# ACB-Light-R1_0-J01.net
KiCad netlist of a schematic drawn in EAGLE
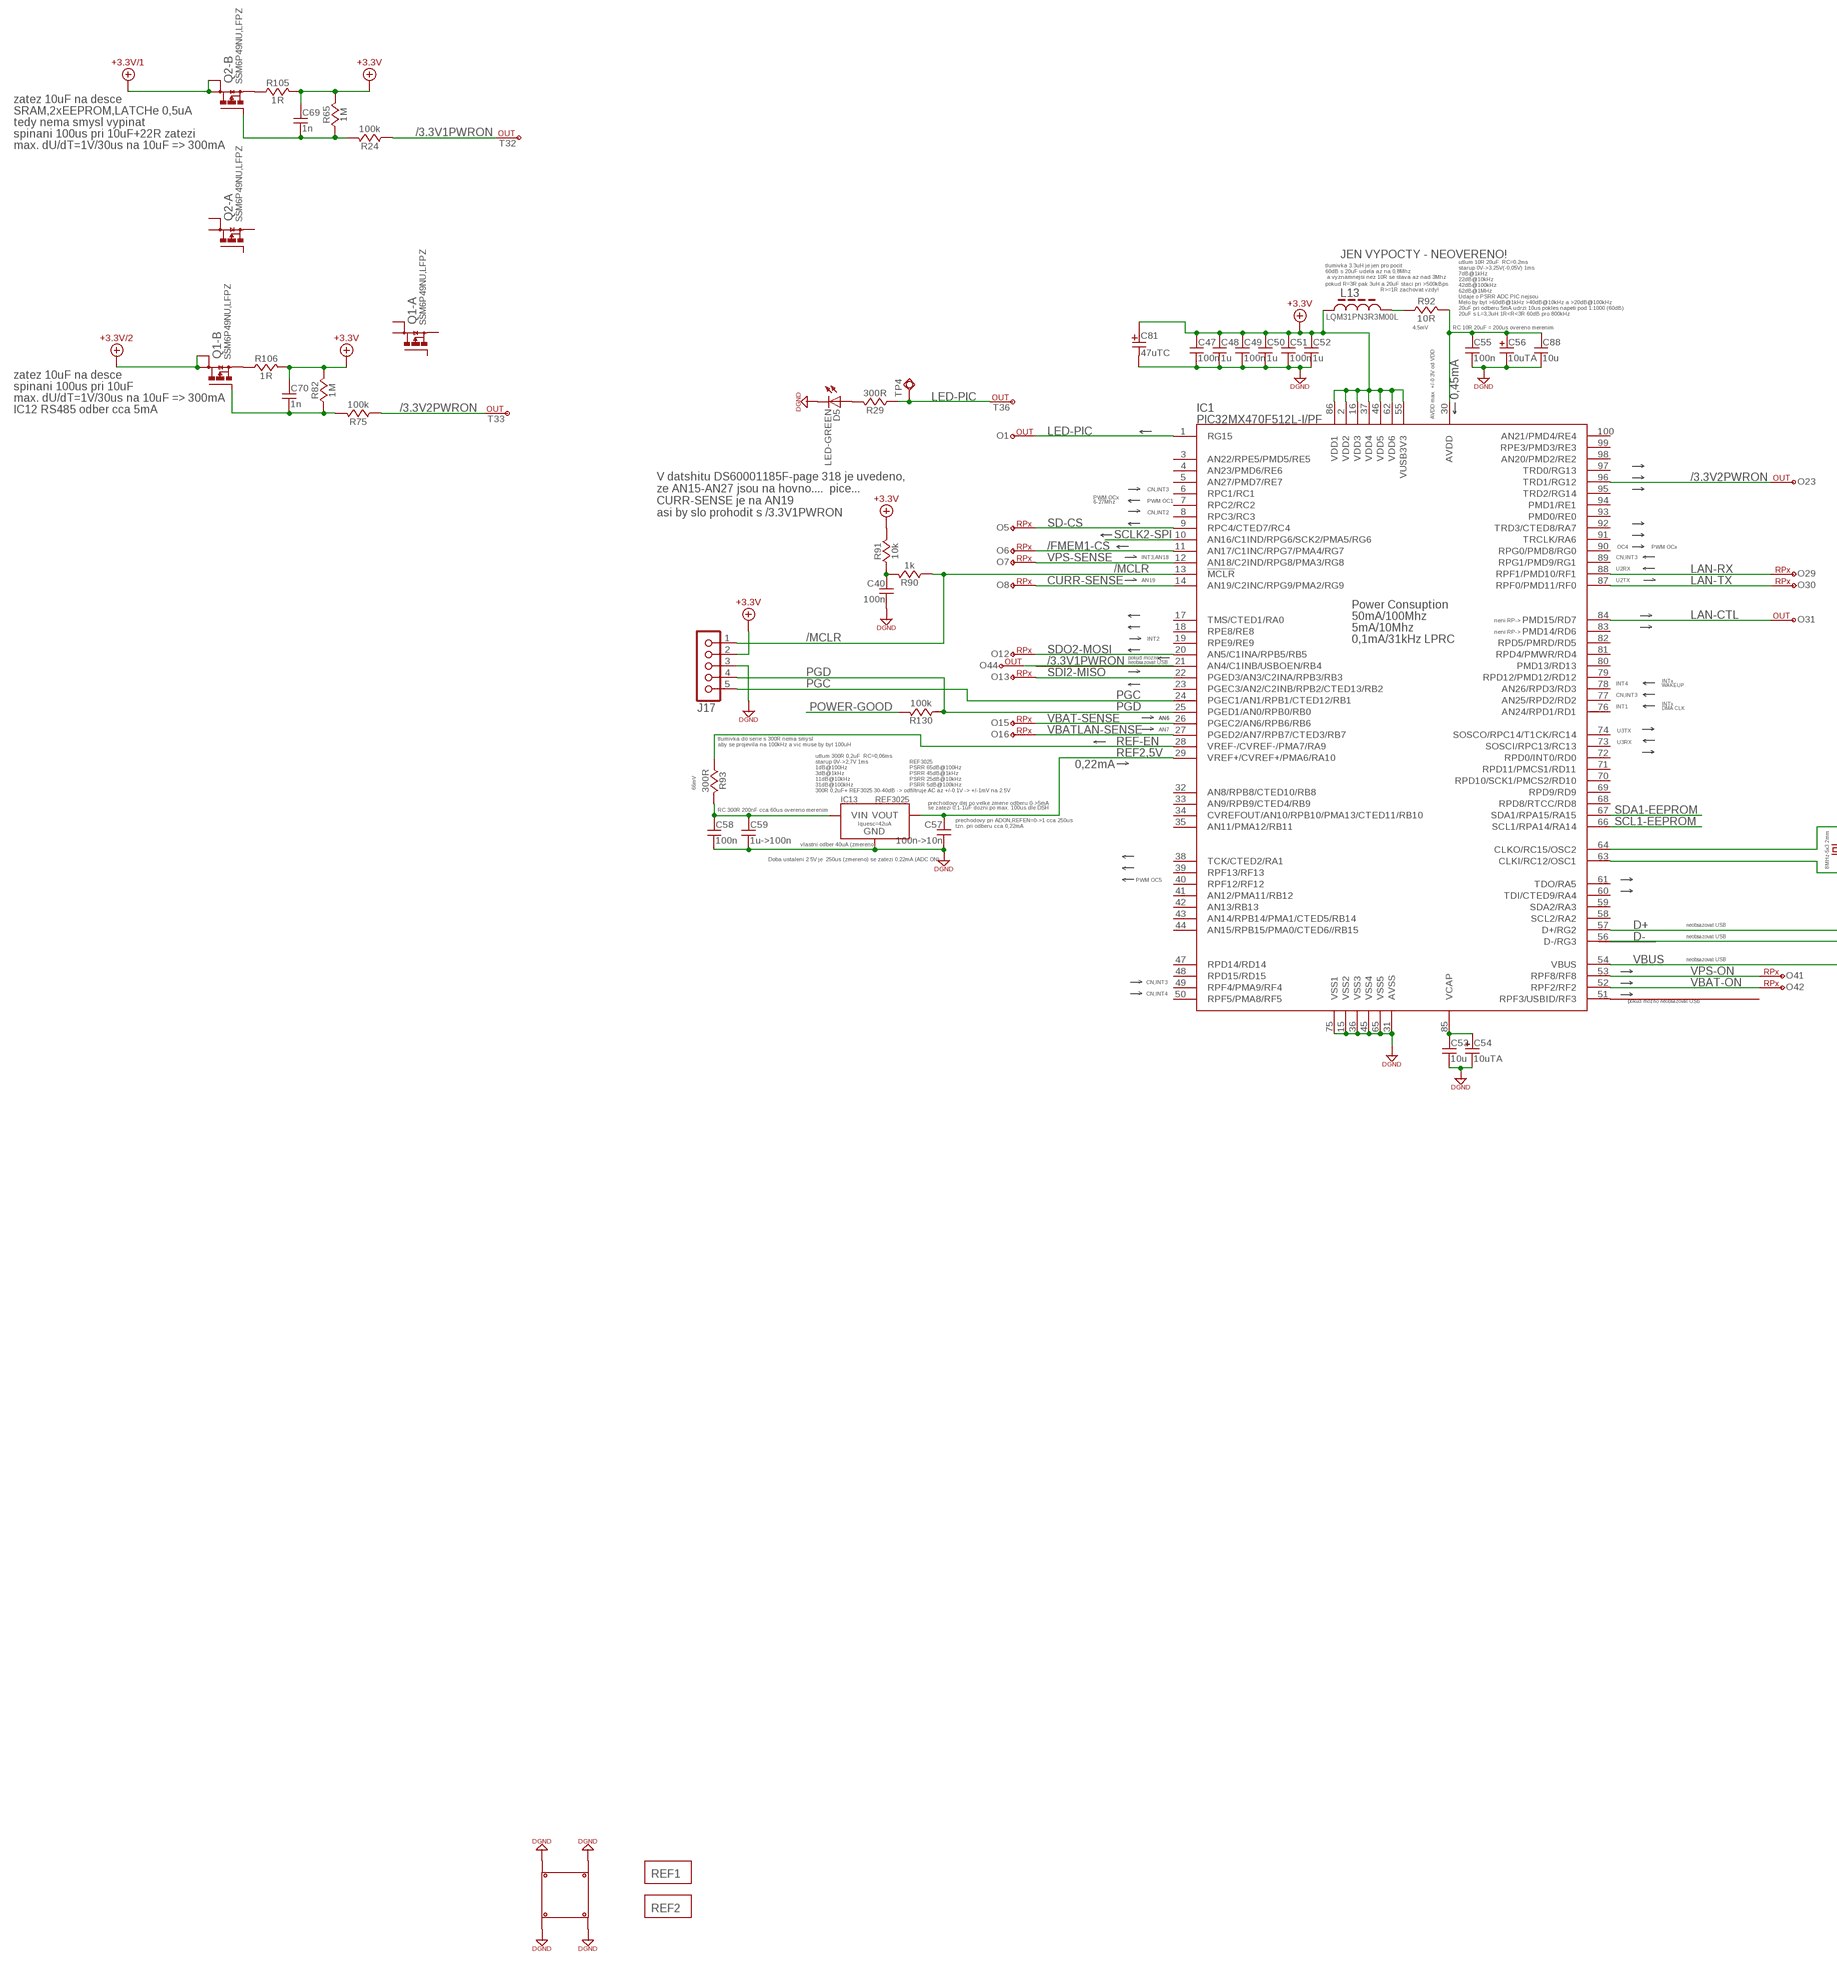
[diagram p0: schematic, sheet 1, part 1 of 3]
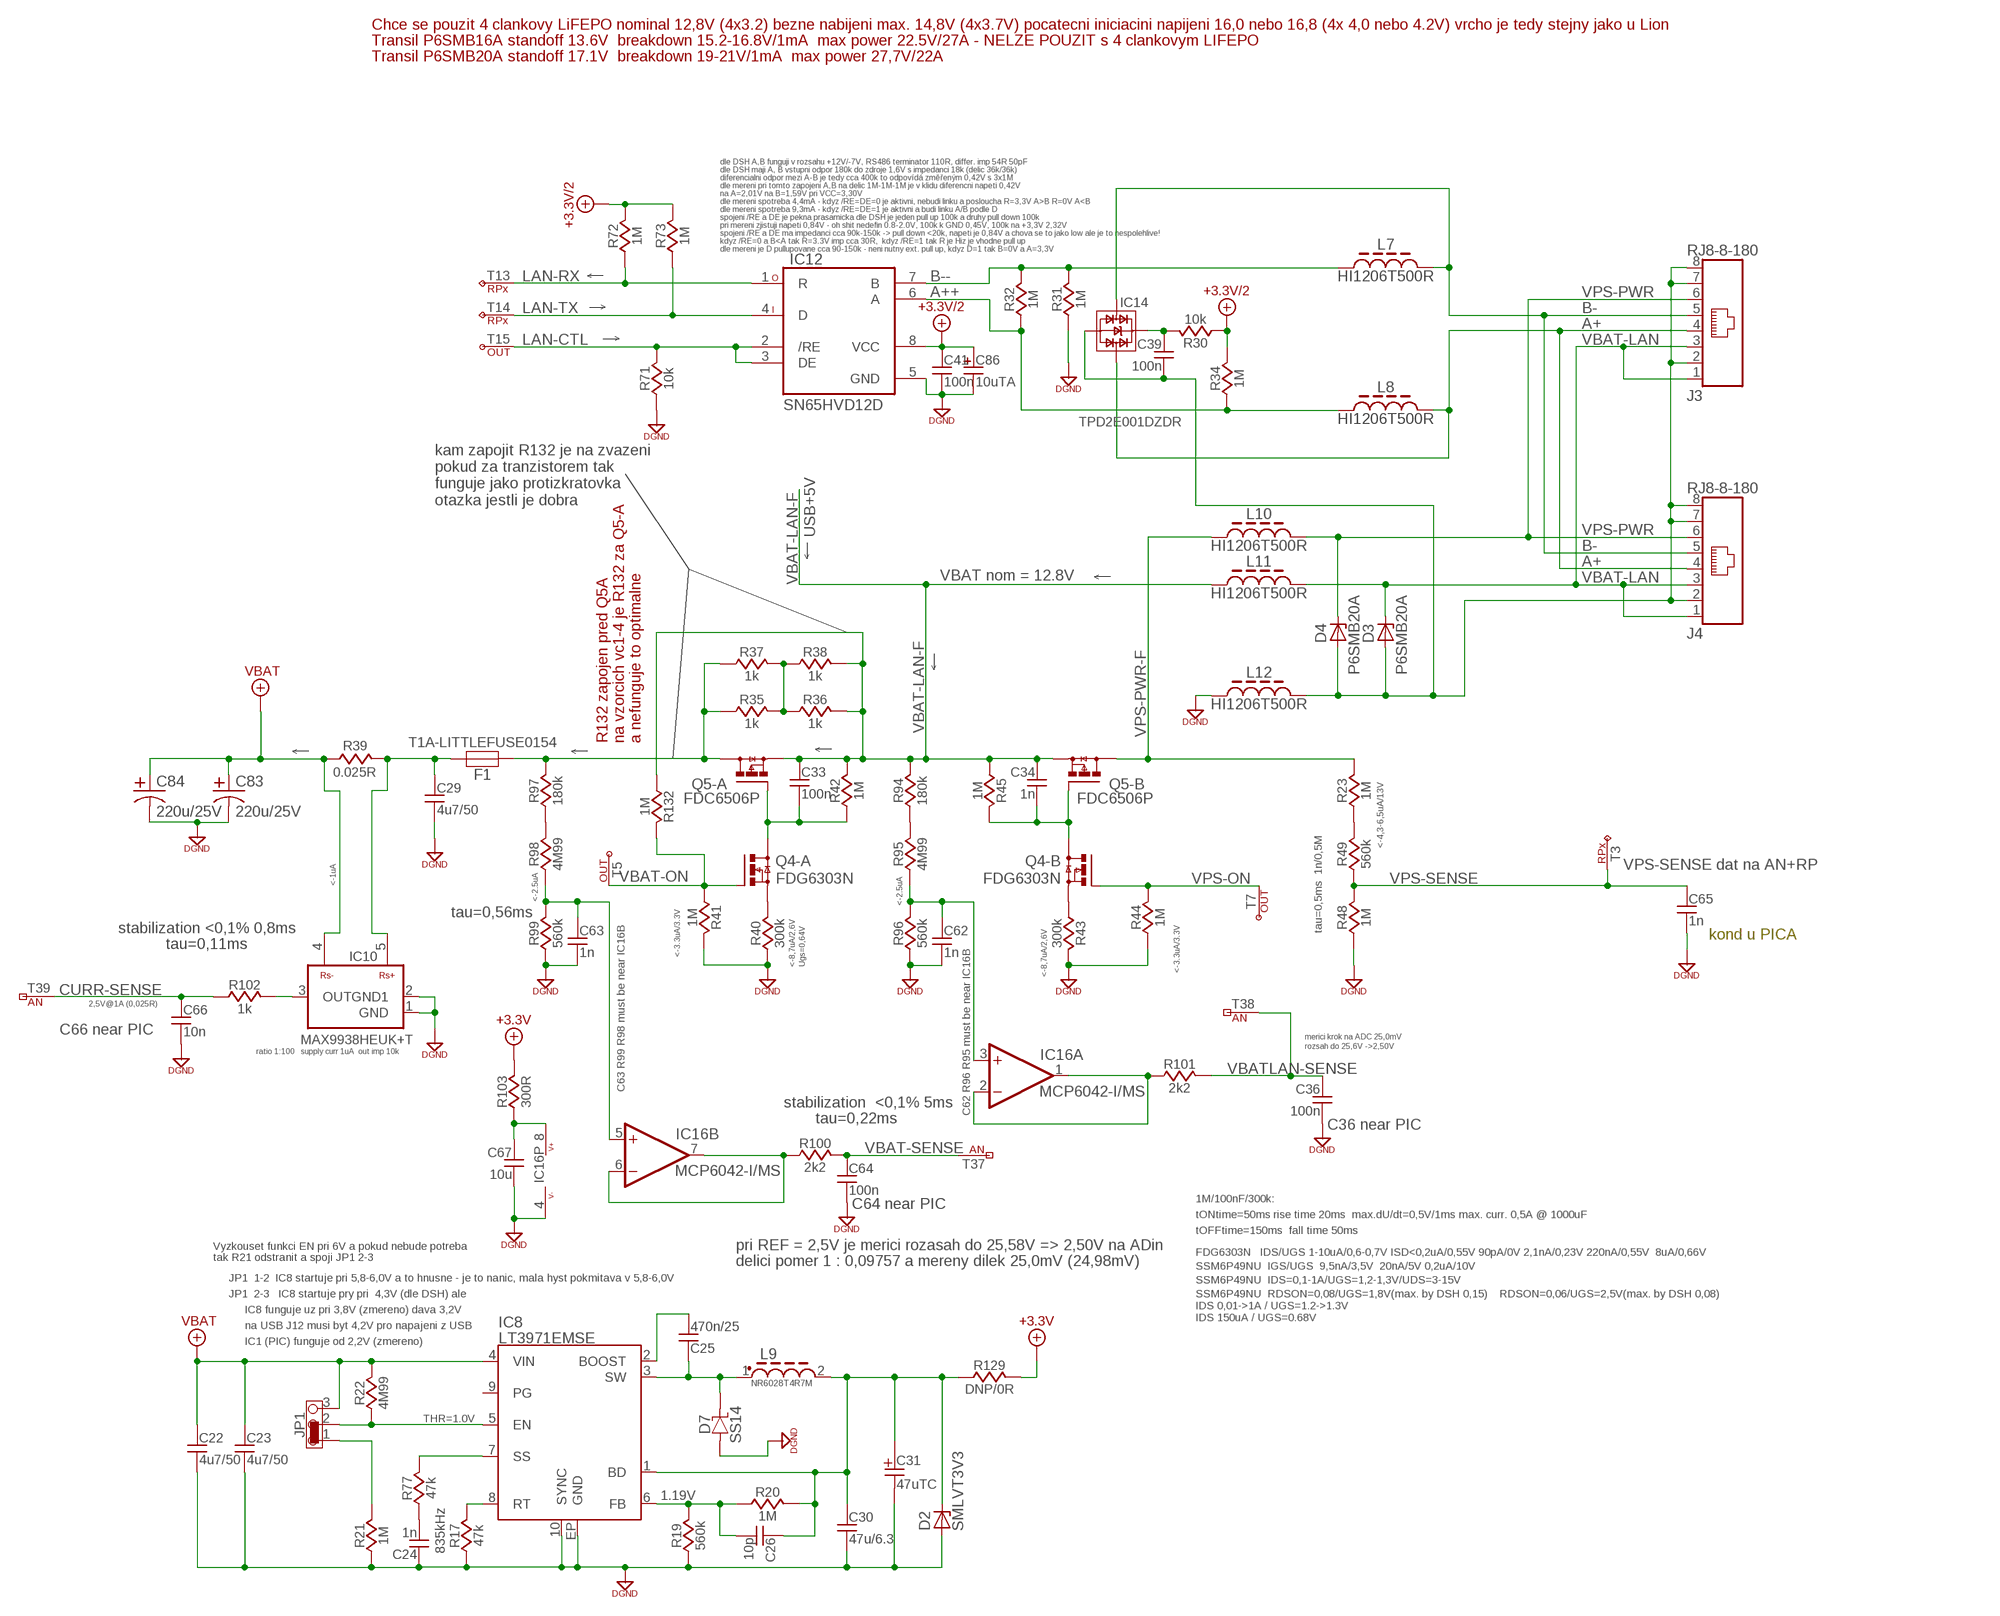
[diagram p1: schematic, sheet 1, part 2 of 3]
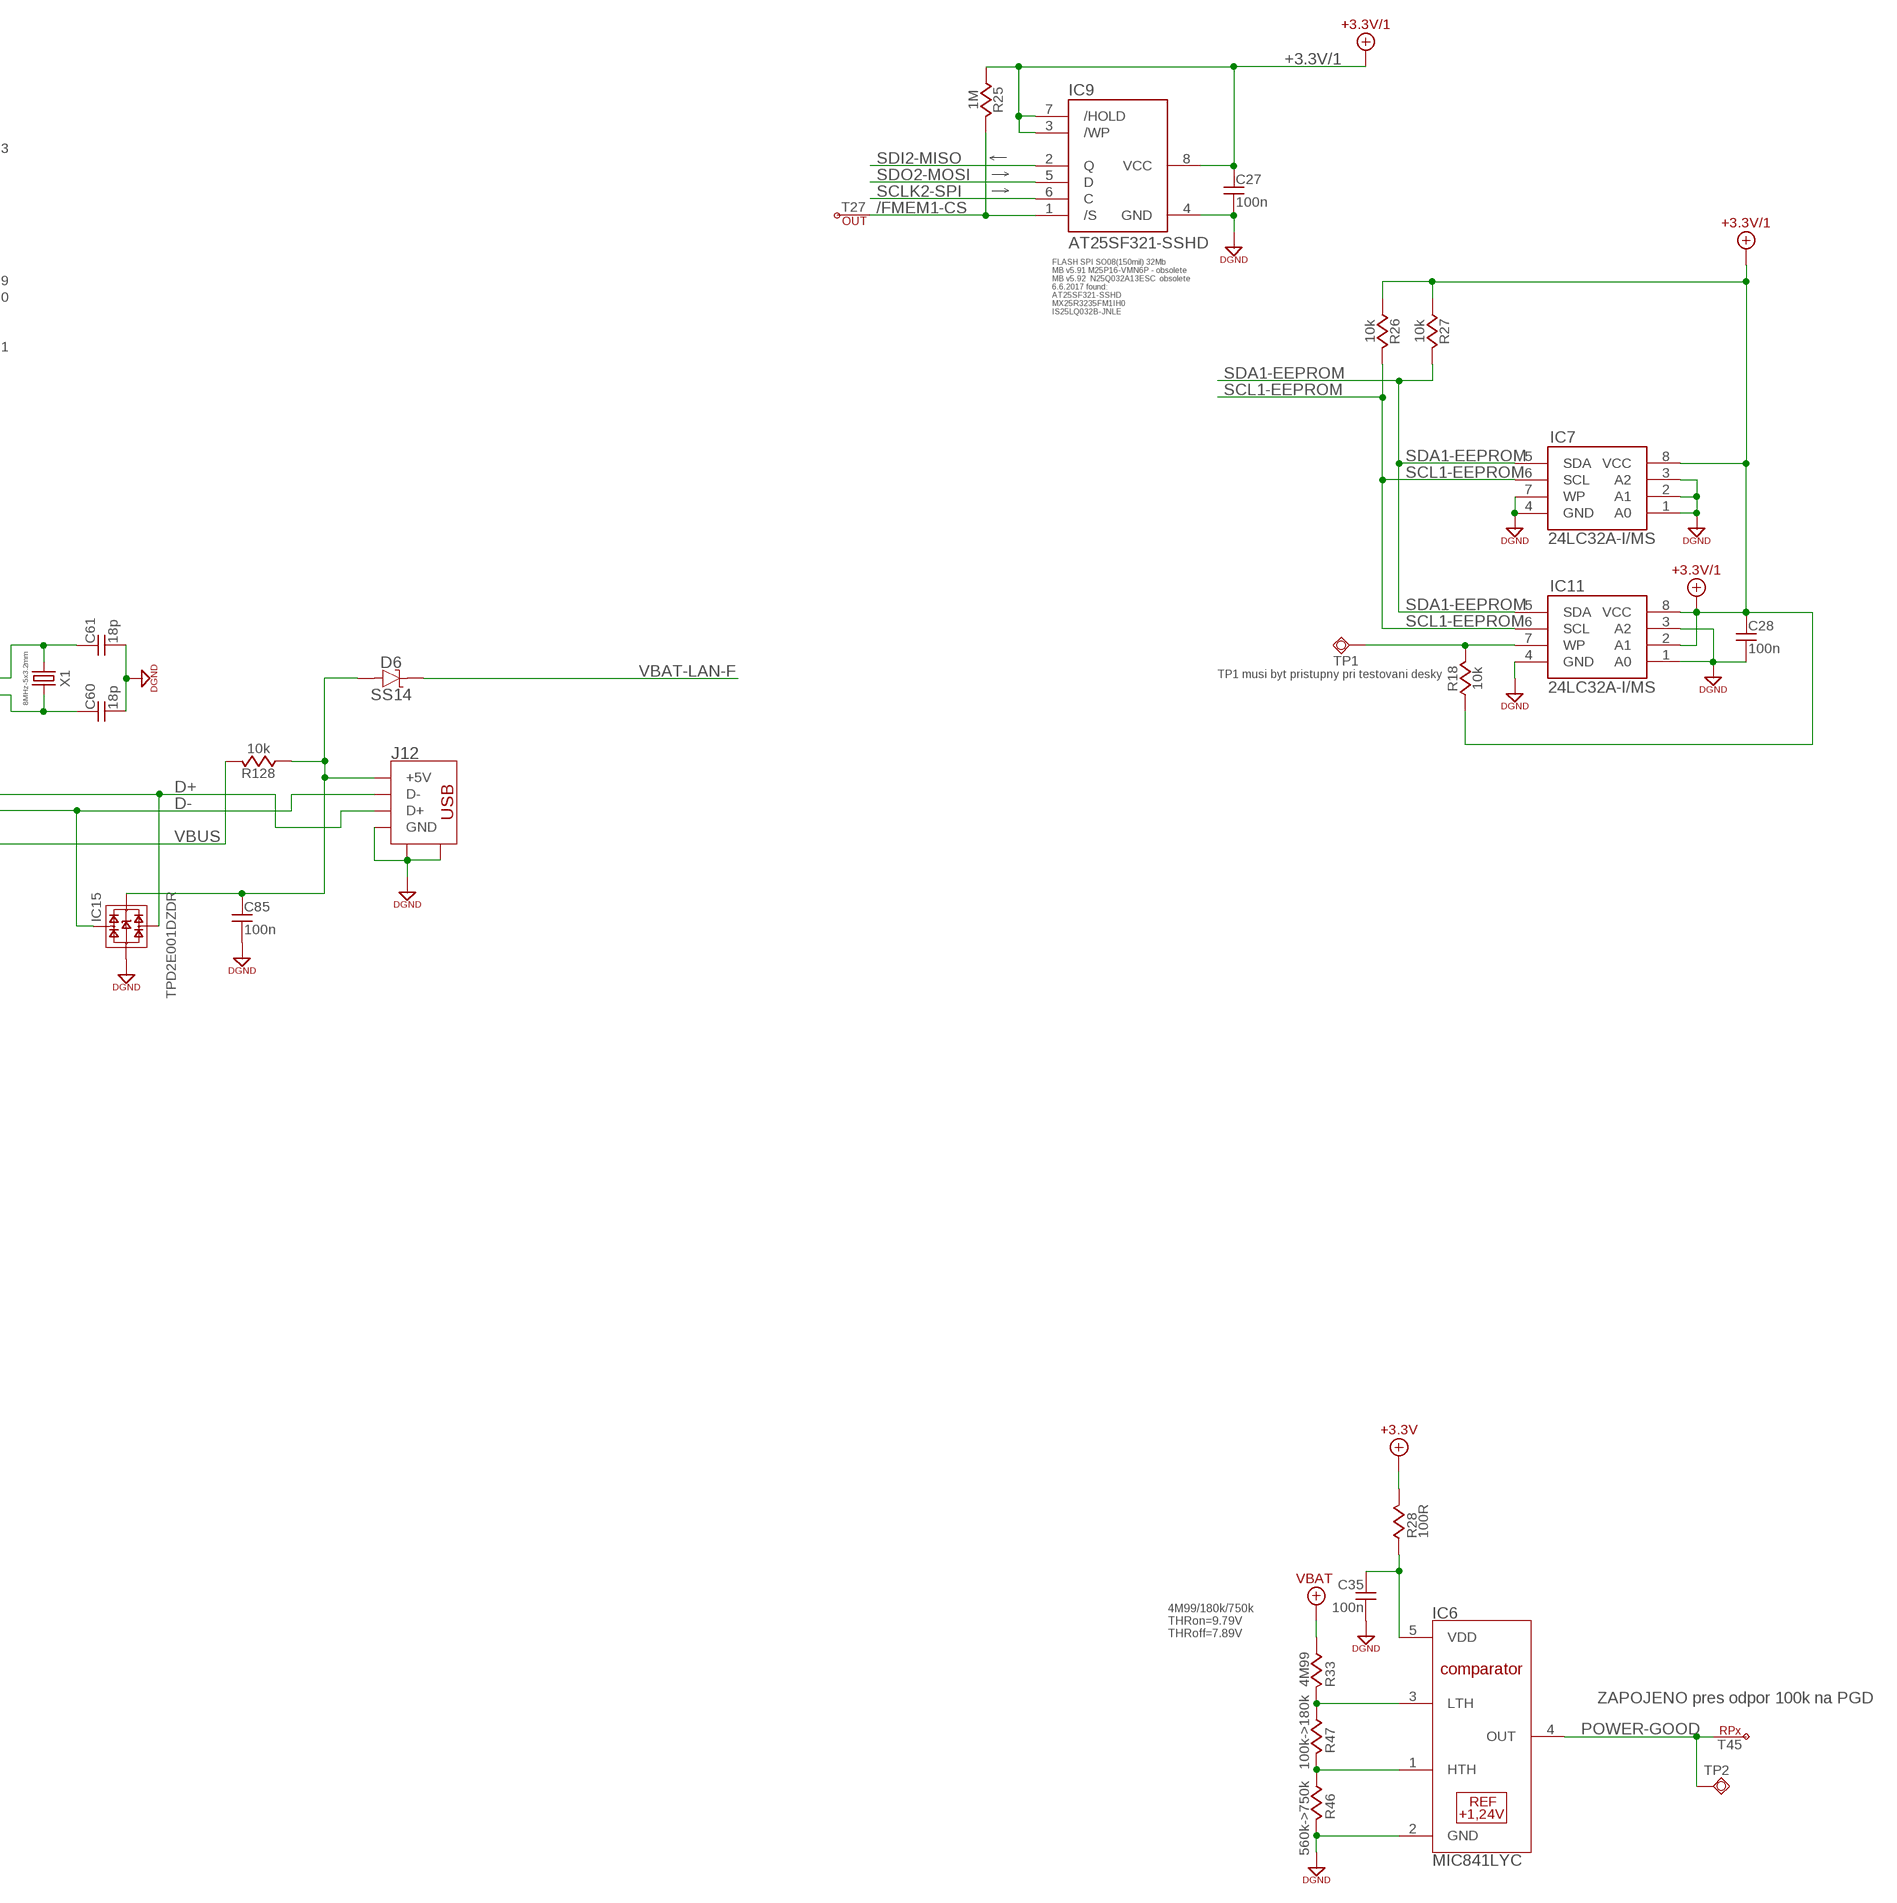
[diagram p2: schematic, sheet 1, part 3 of 3]

(export (version "E")
  (design (tool "Eeschema 10.0.6"))
  (components
    (comp (ref "C22")
      (value "4u7/50")
      (footprint "eagle-import:1206")
      (libsource (lib "eagle-import") (part "C-1206"))
    )
    (comp (ref "C23")
      (value "4u7/50")
      (footprint "eagle-import:1206")
      (libsource (lib "eagle-import") (part "C-1206"))
    )
    (comp (ref "C24")
      (value "1n")
      (footprint "eagle-import:0603")
      (libsource (lib "eagle-import") (part "C-0603"))
    )
    (comp (ref "C25")
      (value "470n/25")
      (footprint "eagle-import:0603")
      (libsource (lib "eagle-import") (part "C-0603"))
    )
    (comp (ref "C26")
      (value "10p")
      (footprint "eagle-import:0603")
      (libsource (lib "eagle-import") (part "C-0603"))
    )
    (comp (ref "C27")
      (value "100n")
      (footprint "eagle-import:0603")
      (libsource (lib "eagle-import") (part "C-0603"))
    )
    (comp (ref "C28")
      (value "100n")
      (footprint "eagle-import:0603")
      (libsource (lib "eagle-import") (part "C-0603"))
    )
    (comp (ref "C29")
      (value "4u7/50")
      (footprint "eagle-import:1206")
      (libsource (lib "eagle-import") (part "C-1206"))
    )
    (comp (ref "C30")
      (value "47u/6.3")
      (footprint "eagle-import:1206")
      (libsource (lib "eagle-import") (part "C-1206"))
    )
    (comp (ref "C31")
      (value "47uTC")
      (footprint "eagle-import:CT-C")
      (libsource (lib "eagle-import") (part "CT-C"))
    )
    (comp (ref "C33")
      (value "100n")
      (footprint "eagle-import:0603")
      (libsource (lib "eagle-import") (part "C-0603"))
    )
    (comp (ref "C34")
      (value "1n")
      (footprint "eagle-import:0603")
      (libsource (lib "eagle-import") (part "C-0603"))
    )
    (comp (ref "C35")
      (value "100n")
      (footprint "eagle-import:0603")
      (libsource (lib "eagle-import") (part "C-0603"))
    )
    (comp (ref "C36")
      (value "100n")
      (footprint "eagle-import:0603")
      (libsource (lib "eagle-import") (part "C-0603"))
    )
    (comp (ref "C39")
      (value "100n")
      (footprint "eagle-import:0603")
      (libsource (lib "eagle-import") (part "C-0603"))
    )
    (comp (ref "C40")
      (value "100n")
      (footprint "eagle-import:0603")
      (libsource (lib "eagle-import") (part "C-0603"))
    )
    (comp (ref "C41")
      (value "100n")
      (footprint "eagle-import:0603")
      (libsource (lib "eagle-import") (part "C-0603"))
    )
    (comp (ref "C47")
      (value "100n")
      (footprint "eagle-import:0603")
      (libsource (lib "eagle-import") (part "C-0603"))
    )
    (comp (ref "C48")
      (value "1u")
      (footprint "eagle-import:0603")
      (libsource (lib "eagle-import") (part "C-0603"))
    )
    (comp (ref "C49")
      (value "100n")
      (footprint "eagle-import:0603")
      (libsource (lib "eagle-import") (part "C-0603"))
    )
    (comp (ref "C50")
      (value "1u")
      (footprint "eagle-import:0603")
      (libsource (lib "eagle-import") (part "C-0603"))
    )
    (comp (ref "C51")
      (value "100n")
      (footprint "eagle-import:0603")
      (libsource (lib "eagle-import") (part "C-0603"))
    )
    (comp (ref "C52")
      (value "1u")
      (footprint "eagle-import:0603")
      (libsource (lib "eagle-import") (part "C-0603"))
    )
    (comp (ref "C53")
      (value "10u")
      (footprint "eagle-import:0603")
      (libsource (lib "eagle-import") (part "C-0603"))
    )
    (comp (ref "C54")
      (value "10uTA")
      (footprint "eagle-import:1206-POL-C")
      (libsource (lib "eagle-import") (part "CT-1206"))
    )
    (comp (ref "C55")
      (value "100n")
      (footprint "eagle-import:0603")
      (libsource (lib "eagle-import") (part "C-0603"))
    )
    (comp (ref "C56")
      (value "10uTA")
      (footprint "eagle-import:1206-POL-C")
      (libsource (lib "eagle-import") (part "CT-1206"))
    )
    (comp (ref "C57")
      (value "100n->10n")
      (footprint "eagle-import:0603")
      (libsource (lib "eagle-import") (part "C-0603"))
    )
    (comp (ref "C58")
      (value "100n")
      (footprint "eagle-import:0603")
      (libsource (lib "eagle-import") (part "C-0603"))
    )
    (comp (ref "C59")
      (value "1u->100n")
      (footprint "eagle-import:0603")
      (libsource (lib "eagle-import") (part "C-0603"))
    )
    (comp (ref "C60")
      (value "18p")
      (footprint "eagle-import:0603")
      (libsource (lib "eagle-import") (part "C-0603"))
    )
    (comp (ref "C61")
      (value "18p")
      (footprint "eagle-import:0603")
      (libsource (lib "eagle-import") (part "C-0603"))
    )
    (comp (ref "C62")
      (value "1n")
      (footprint "eagle-import:0603")
      (libsource (lib "eagle-import") (part "C-0603"))
    )
    (comp (ref "C63")
      (value "1n")
      (footprint "eagle-import:0603")
      (libsource (lib "eagle-import") (part "C-0603"))
    )
    (comp (ref "C64")
      (value "100n")
      (footprint "eagle-import:0603")
      (libsource (lib "eagle-import") (part "C-0603"))
    )
    (comp (ref "C65")
      (value "1n")
      (footprint "eagle-import:0603")
      (libsource (lib "eagle-import") (part "C-0603"))
    )
    (comp (ref "C66")
      (value "10n")
      (footprint "eagle-import:0603")
      (libsource (lib "eagle-import") (part "C-0603"))
    )
    (comp (ref "C67")
      (value "10u")
      (footprint "eagle-import:0603")
      (libsource (lib "eagle-import") (part "C-0603"))
    )
    (comp (ref "C69")
      (value "1n")
      (footprint "eagle-import:0603")
      (libsource (lib "eagle-import") (part "C-0603"))
    )
    (comp (ref "C70")
      (value "1n")
      (footprint "eagle-import:0603")
      (libsource (lib "eagle-import") (part "C-0603"))
    )
    (comp (ref "C81")
      (value "47uTC")
      (footprint "eagle-import:CT-C")
      (libsource (lib "eagle-import") (part "CT-C"))
    )
    (comp (ref "C83")
      (value "220u/25V")
      (footprint "eagle-import:CAP_8MM_DIA_SMT")
      (libsource (lib "eagle-import") (part "CAP-ELEC-SMD-8MM"))
    )
    (comp (ref "C84")
      (value "220u/25V")
      (footprint "eagle-import:CAP_8MM_DIA_SMT")
      (libsource (lib "eagle-import") (part "CAP-ELEC-SMD-8MM"))
    )
    (comp (ref "C85")
      (value "100n")
      (footprint "eagle-import:0603")
      (libsource (lib "eagle-import") (part "C-0603"))
    )
    (comp (ref "C86")
      (value "10uTA")
      (footprint "eagle-import:1206-POL-C")
      (libsource (lib "eagle-import") (part "CT-1206"))
    )
    (comp (ref "C88")
      (value "10u")
      (footprint "eagle-import:0603")
      (libsource (lib "eagle-import") (part "C-0603"))
    )
    (comp (ref "D2")
      (value "SMLVT3V3")
      (footprint "eagle-import:SMA")
      (libsource (lib "eagle-import") (part "SMLVT3V3"))
    )
    (comp (ref "D3")
      (value "P6SMB20A")
      (footprint "eagle-import:SMB")
      (libsource (lib "eagle-import") (part "P6SMB"))
    )
    (comp (ref "D4")
      (value "P6SMB20A")
      (footprint "eagle-import:SMB")
      (libsource (lib "eagle-import") (part "P6SMB"))
    )
    (comp (ref "D5")
      (value "LED-GREEN")
      (footprint "eagle-import:0805-POL-D")
      (libsource (lib "eagle-import") (part "LED-0805"))
    )
    (comp (ref "D6")
      (value "SS14")
      (footprint "eagle-import:SMA")
      (libsource (lib "eagle-import") (part "DS-SMA"))
    )
    (comp (ref "D7")
      (value "SS14")
      (footprint "eagle-import:SMA")
      (libsource (lib "eagle-import") (part "DS-SMA"))
    )
    (comp (ref "F1")
      (value "T1A-LITTLEFUSE0154")
      (footprint "eagle-import:LITTLEFUSE0154")
      (libsource (lib "eagle-import") (part "POJISTKA-LITTLEFUSE0154"))
    )
    (comp (ref "IC1")
      (value "PIC32MX470F512L-I/PF")
      (footprint "eagle-import:TQFP100_14X14_0,5MM")
      (libsource (lib "eagle-import") (part "PIC32MX470F512L-I/PF"))
    )
    (comp (ref "IC6")
      (value "MIC841LYC")
      (footprint "eagle-import:SC-70-5")
      (libsource (lib "eagle-import") (part "MIC841LYC"))
    )
    (comp (ref "IC7")
      (value "24LC32A-I/MS")
      (footprint "eagle-import:MSOP-08")
      (libsource (lib "eagle-import") (part "24-I/MS"))
    )
    (comp (ref "IC8")
      (value "LT3971EMSE")
      (footprint "eagle-import:MSOP10EXP")
      (libsource (lib "eagle-import") (part "LT3971EMSE"))
    )
    (comp (ref "IC9")
      (value "AT25SF321-SSHD")
      (footprint "eagle-import:SO-08")
      (libsource (lib "eagle-import") (part "M25P16-VMN6P"))
    )
    (comp (ref "IC10")
      (value "MAX9938HEUK+T")
      (footprint "eagle-import:SOT23-5")
      (libsource (lib "eagle-import") (part "TSM9938HEUK+T"))
    )
    (comp (ref "IC11")
      (value "24LC32A-I/MS")
      (footprint "eagle-import:MSOP-08")
      (libsource (lib "eagle-import") (part "24-I/MS"))
    )
    (comp (ref "IC12")
      (value "SN65HVD12D")
      (footprint "eagle-import:SO08")
      (libsource (lib "eagle-import") (part "SN65HVD3082ED"))
    )
    (comp (ref "IC13")
      (value "REF3025")
      (footprint "eagle-import:SOT23")
      (libsource (lib "eagle-import") (part "REF3025"))
    )
    (comp (ref "IC14")
      (value "TPD2E001DZDR")
      (footprint "eagle-import:SOT-143")
      (libsource (lib "eagle-import") (part "SR05.TCT"))
    )
    (comp (ref "IC15")
      (value "TPD2E001DZDR")
      (footprint "eagle-import:SOT-143")
      (libsource (lib "eagle-import") (part "SR05.TCT"))
    )
    (comp (ref "IC16")
      (value "MCP6042-I/MS")
      (footprint "eagle-import:MSOP-08")
      (libsource (lib "eagle-import") (part "MCP6042-I/MS"))
    )
    (comp (ref "J3")
      (value "RJ8-8-180")
      (footprint "eagle-import:RJ8-8-180")
      (libsource (lib "eagle-import") (part "RJ8-8-180"))
    )
    (comp (ref "J4")
      (value "RJ8-8-180")
      (footprint "eagle-import:RJ8-8-180")
      (libsource (lib "eagle-import") (part "RJ8-8-180"))
    )
    (comp (ref "J12")
      (value "USB_A_180")
      (footprint "eagle-import:USB_B_180")
      (libsource (lib "eagle-import") (part "USB_B_180"))
    )
    (comp (ref "J17")
      (value "DNP-open-hole")
      (footprint "eagle-import:MA05-1")
      (libsource (lib "eagle-import") (part "MA05-1"))
    )
    (comp (ref "JP1")
      (value "JP3CLOSE12")
      (footprint "eagle-import:JP3CLOSE12")
      (libsource (lib "eagle-import") (part "JP3CLOSE12"))
    )
    (comp (ref "L7")
      (value "HI1206T500R")
      (footprint "eagle-import:1206")
      (libsource (lib "eagle-import") (part "L-1206"))
    )
    (comp (ref "L8")
      (value "HI1206T500R")
      (footprint "eagle-import:1206")
      (libsource (lib "eagle-import") (part "L-1206"))
    )
    (comp (ref "L9")
      (value "NR6028T4R7M")
      (footprint "eagle-import:NR6028")
      (libsource (lib "eagle-import") (part "NR6028"))
    )
    (comp (ref "L10")
      (value "HI1206T500R")
      (footprint "eagle-import:1206")
      (libsource (lib "eagle-import") (part "L-1206"))
    )
    (comp (ref "L11")
      (value "HI1206T500R")
      (footprint "eagle-import:1206")
      (libsource (lib "eagle-import") (part "L-1206"))
    )
    (comp (ref "L12")
      (value "HI1206T500R")
      (footprint "eagle-import:1206")
      (libsource (lib "eagle-import") (part "L-1206"))
    )
    (comp (ref "L13")
      (value "LQM31PN3R3M00L")
      (footprint "eagle-import:1206")
      (libsource (lib "eagle-import") (part "L-1206"))
    )
    (comp (ref "O1")
      (value "PIC-OUT")
      (footprint "eagle-import:TEMP-PAD")
      (libsource (lib "eagle-import") (part "PIC-OUT"))
    )
    (comp (ref "O5")
      (value "PIC-RPX")
      (footprint "eagle-import:TEMP-PAD")
      (libsource (lib "eagle-import") (part "PIC-RPX"))
    )
    (comp (ref "O6")
      (value "PIC-RPX")
      (footprint "eagle-import:TEMP-PAD")
      (libsource (lib "eagle-import") (part "PIC-RPX"))
    )
    (comp (ref "O7")
      (value "PIC-RPX")
      (footprint "eagle-import:TEMP-PAD")
      (libsource (lib "eagle-import") (part "PIC-RPX"))
    )
    (comp (ref "O8")
      (value "PIC-RPX")
      (footprint "eagle-import:TEMP-PAD")
      (libsource (lib "eagle-import") (part "PIC-RPX"))
    )
    (comp (ref "O12")
      (value "PIC-RPX")
      (footprint "eagle-import:TEMP-PAD")
      (libsource (lib "eagle-import") (part "PIC-RPX"))
    )
    (comp (ref "O13")
      (value "PIC-RPX")
      (footprint "eagle-import:TEMP-PAD")
      (libsource (lib "eagle-import") (part "PIC-RPX"))
    )
    (comp (ref "O15")
      (value "PIC-RPX")
      (footprint "eagle-import:TEMP-PAD")
      (libsource (lib "eagle-import") (part "PIC-RPX"))
    )
    (comp (ref "O16")
      (value "PIC-RPX")
      (footprint "eagle-import:TEMP-PAD")
      (libsource (lib "eagle-import") (part "PIC-RPX"))
    )
    (comp (ref "O23")
      (value "PIC-OUT")
      (footprint "eagle-import:TEMP-PAD")
      (libsource (lib "eagle-import") (part "PIC-OUT"))
    )
    (comp (ref "O29")
      (value "PIC-RPX")
      (footprint "eagle-import:TEMP-PAD")
      (libsource (lib "eagle-import") (part "PIC-RPX"))
    )
    (comp (ref "O30")
      (value "PIC-RPX")
      (footprint "eagle-import:TEMP-PAD")
      (libsource (lib "eagle-import") (part "PIC-RPX"))
    )
    (comp (ref "O31")
      (value "PIC-OUT")
      (footprint "eagle-import:TEMP-PAD")
      (libsource (lib "eagle-import") (part "PIC-OUT"))
    )
    (comp (ref "O41")
      (value "PIC-RPX")
      (footprint "eagle-import:TEMP-PAD")
      (libsource (lib "eagle-import") (part "PIC-RPX"))
    )
    (comp (ref "O42")
      (value "PIC-RPX")
      (footprint "eagle-import:TEMP-PAD")
      (libsource (lib "eagle-import") (part "PIC-RPX"))
    )
    (comp (ref "O44")
      (value "PIC-OUT")
      (footprint "eagle-import:TEMP-PAD")
      (libsource (lib "eagle-import") (part "PIC-OUT"))
    )
    (comp (ref "PCB1")
      (value "PCB-ACB")
      (footprint "eagle-import:PCB-ACB")
      (libsource (lib "eagle-import") (part "PCB-ACB-1"))
    )
    (comp (ref "Q1")
      (value "SSM6P49NU,LFPZ")
      (footprint "eagle-import:MICRO_FET")
      (libsource (lib "eagle-import") (part "SSM6P49PZNU,LF"))
    )
    (comp (ref "Q2")
      (value "SSM6P49NU,LFPZ")
      (footprint "eagle-import:MICRO_FET")
      (libsource (lib "eagle-import") (part "SSM6P49PZNU,LF"))
    )
    (comp (ref "Q4")
      (value "FDG6303N")
      (footprint "eagle-import:SC70-6")
      (libsource (lib "eagle-import") (part "FDG6303N"))
    )
    (comp (ref "Q5")
      (value "FDC6506P")
      (footprint "eagle-import:SSOT-6")
      (libsource (lib "eagle-import") (part "FDC6506D"))
    )
    (comp (ref "R17")
      (value "47k")
      (footprint "eagle-import:0603")
      (libsource (lib "eagle-import") (part "R-0603"))
    )
    (comp (ref "R18")
      (value "10k")
      (footprint "eagle-import:0603")
      (libsource (lib "eagle-import") (part "R-0603"))
    )
    (comp (ref "R19")
      (value "560k")
      (footprint "eagle-import:0603")
      (libsource (lib "eagle-import") (part "R-0603"))
    )
    (comp (ref "R20")
      (value "1M")
      (footprint "eagle-import:0603")
      (libsource (lib "eagle-import") (part "R-0603"))
    )
    (comp (ref "R21")
      (value "1M")
      (footprint "eagle-import:0603")
      (libsource (lib "eagle-import") (part "R-0603"))
    )
    (comp (ref "R22")
      (value "4M99")
      (footprint "eagle-import:0603")
      (libsource (lib "eagle-import") (part "R-0603"))
    )
    (comp (ref "R23")
      (value "1M")
      (footprint "eagle-import:0603")
      (libsource (lib "eagle-import") (part "R-0603"))
    )
    (comp (ref "R24")
      (value "100k")
      (footprint "eagle-import:0603")
      (libsource (lib "eagle-import") (part "R-0603"))
    )
    (comp (ref "R25")
      (value "1M")
      (footprint "eagle-import:0603")
      (libsource (lib "eagle-import") (part "R-0603"))
    )
    (comp (ref "R26")
      (value "10k")
      (footprint "eagle-import:0603")
      (libsource (lib "eagle-import") (part "R-0603"))
    )
    (comp (ref "R27")
      (value "10k")
      (footprint "eagle-import:0603")
      (libsource (lib "eagle-import") (part "R-0603"))
    )
    (comp (ref "R28")
      (value "100R")
      (footprint "eagle-import:0603")
      (libsource (lib "eagle-import") (part "R-0603"))
    )
    (comp (ref "R29")
      (value "300R")
      (footprint "eagle-import:0603")
      (libsource (lib "eagle-import") (part "R-0603"))
    )
    (comp (ref "R30")
      (value "10k")
      (footprint "eagle-import:0603")
      (libsource (lib "eagle-import") (part "R-0603"))
    )
    (comp (ref "R31")
      (value "1M")
      (footprint "eagle-import:0603")
      (libsource (lib "eagle-import") (part "R-0603"))
    )
    (comp (ref "R32")
      (value "1M")
      (footprint "eagle-import:0603")
      (libsource (lib "eagle-import") (part "R-0603"))
    )
    (comp (ref "R33")
      (value "4M99")
      (footprint "eagle-import:0603")
      (libsource (lib "eagle-import") (part "R-0603"))
    )
    (comp (ref "R34")
      (value "1M")
      (footprint "eagle-import:0603")
      (libsource (lib "eagle-import") (part "R-0603"))
    )
    (comp (ref "R35")
      (value "1k")
      (footprint "eagle-import:0805")
      (libsource (lib "eagle-import") (part "R-0805"))
    )
    (comp (ref "R36")
      (value "1k")
      (footprint "eagle-import:0805")
      (libsource (lib "eagle-import") (part "R-0805"))
    )
    (comp (ref "R37")
      (value "1k")
      (footprint "eagle-import:0805")
      (libsource (lib "eagle-import") (part "R-0805"))
    )
    (comp (ref "R38")
      (value "1k")
      (footprint "eagle-import:0805")
      (libsource (lib "eagle-import") (part "R-0805"))
    )
    (comp (ref "R39")
      (value "0.025R")
      (footprint "eagle-import:0805")
      (libsource (lib "eagle-import") (part "R-0805"))
    )
    (comp (ref "R40")
      (value "300k")
      (footprint "eagle-import:0603")
      (libsource (lib "eagle-import") (part "R-0603"))
    )
    (comp (ref "R41")
      (value "1M")
      (footprint "eagle-import:0603")
      (libsource (lib "eagle-import") (part "R-0603"))
    )
    (comp (ref "R42")
      (value "1M")
      (footprint "eagle-import:0603")
      (libsource (lib "eagle-import") (part "R-0603"))
    )
    (comp (ref "R43")
      (value "300k")
      (footprint "eagle-import:0603")
      (libsource (lib "eagle-import") (part "R-0603"))
    )
    (comp (ref "R44")
      (value "1M")
      (footprint "eagle-import:0603")
      (libsource (lib "eagle-import") (part "R-0603"))
    )
    (comp (ref "R45")
      (value "1M")
      (footprint "eagle-import:0603")
      (libsource (lib "eagle-import") (part "R-0603"))
    )
    (comp (ref "R46")
      (value "560k->750k")
      (footprint "eagle-import:0603")
      (libsource (lib "eagle-import") (part "R-0603"))
    )
    (comp (ref "R47")
      (value "100k->180k")
      (footprint "eagle-import:0603")
      (libsource (lib "eagle-import") (part "R-0603"))
    )
    (comp (ref "R48")
      (value "1M")
      (footprint "eagle-import:0603")
      (libsource (lib "eagle-import") (part "R-0603"))
    )
    (comp (ref "R49")
      (value "560k")
      (footprint "eagle-import:0603")
      (libsource (lib "eagle-import") (part "R-0603"))
    )
    (comp (ref "R65")
      (value "1M")
      (footprint "eagle-import:0603")
      (libsource (lib "eagle-import") (part "R-0603"))
    )
    (comp (ref "R71")
      (value "10k")
      (footprint "eagle-import:0603")
      (libsource (lib "eagle-import") (part "R-0603"))
    )
    (comp (ref "R72")
      (value "1M")
      (footprint "eagle-import:0603")
      (libsource (lib "eagle-import") (part "R-0603"))
    )
    (comp (ref "R73")
      (value "1M")
      (footprint "eagle-import:0603")
      (libsource (lib "eagle-import") (part "R-0603"))
    )
    (comp (ref "R75")
      (value "100k")
      (footprint "eagle-import:0603")
      (libsource (lib "eagle-import") (part "R-0603"))
    )
    (comp (ref "R77")
      (value "47k")
      (footprint "eagle-import:0603")
      (libsource (lib "eagle-import") (part "R-0603"))
    )
    (comp (ref "R82")
      (value "1M")
      (footprint "eagle-import:0603")
      (libsource (lib "eagle-import") (part "R-0603"))
    )
    (comp (ref "R90")
      (value "1k")
      (footprint "eagle-import:0603")
      (libsource (lib "eagle-import") (part "R-0603"))
    )
    (comp (ref "R91")
      (value "10k")
      (footprint "eagle-import:0603")
      (libsource (lib "eagle-import") (part "R-0603"))
    )
    (comp (ref "R92")
      (value "10R")
      (footprint "eagle-import:0603")
      (libsource (lib "eagle-import") (part "R-0603"))
    )
    (comp (ref "R93")
      (value "300R")
      (footprint "eagle-import:0603")
      (libsource (lib "eagle-import") (part "R-0603"))
    )
    (comp (ref "R94")
      (value "180k")
      (footprint "eagle-import:0603")
      (libsource (lib "eagle-import") (part "R-0603"))
    )
    (comp (ref "R95")
      (value "4M99")
      (footprint "eagle-import:0603")
      (libsource (lib "eagle-import") (part "R-0603"))
    )
    (comp (ref "R96")
      (value "560k")
      (footprint "eagle-import:0603")
      (libsource (lib "eagle-import") (part "R-0603"))
    )
    (comp (ref "R97")
      (value "180k")
      (footprint "eagle-import:0603")
      (libsource (lib "eagle-import") (part "R-0603"))
    )
    (comp (ref "R98")
      (value "4M99")
      (footprint "eagle-import:0603")
      (libsource (lib "eagle-import") (part "R-0603"))
    )
    (comp (ref "R99")
      (value "560k")
      (footprint "eagle-import:0603")
      (libsource (lib "eagle-import") (part "R-0603"))
    )
    (comp (ref "R100")
      (value "2k2")
      (footprint "eagle-import:0603")
      (libsource (lib "eagle-import") (part "R-0603"))
    )
    (comp (ref "R101")
      (value "2k2")
      (footprint "eagle-import:0603")
      (libsource (lib "eagle-import") (part "R-0603"))
    )
    (comp (ref "R102")
      (value "1k")
      (footprint "eagle-import:0603")
      (libsource (lib "eagle-import") (part "R-0603"))
    )
    (comp (ref "R103")
      (value "300R")
      (footprint "eagle-import:0603")
      (libsource (lib "eagle-import") (part "R-0603"))
    )
    (comp (ref "R105")
      (value "1R")
      (footprint "eagle-import:0805")
      (libsource (lib "eagle-import") (part "R-0805"))
    )
    (comp (ref "R106")
      (value "1R")
      (footprint "eagle-import:0805")
      (libsource (lib "eagle-import") (part "R-0805"))
    )
    (comp (ref "R128")
      (value "10k")
      (footprint "eagle-import:0603")
      (libsource (lib "eagle-import") (part "R-0603"))
    )
    (comp (ref "R129")
      (value "DNP/0R")
      (footprint "eagle-import:0603")
      (libsource (lib "eagle-import") (part "R-0603"))
    )
    (comp (ref "R130")
      (value "100k")
      (footprint "eagle-import:0603")
      (libsource (lib "eagle-import") (part "R-0603"))
    )
    (comp (ref "R132")
      (value "1M")
      (footprint "eagle-import:0603")
      (libsource (lib "eagle-import") (part "R-0603"))
    )
    (comp (ref "REF1")
      (value "REF")
      (footprint "eagle-import:REF")
      (libsource (lib "eagle-import") (part "REF"))
    )
    (comp (ref "REF2")
      (value "REF")
      (footprint "eagle-import:REF")
      (libsource (lib "eagle-import") (part "REF"))
    )
    (comp (ref "T3")
      (value "PIC-RPX")
      (footprint "eagle-import:TEMP-PAD")
      (libsource (lib "eagle-import") (part "PIC-RPX"))
    )
    (comp (ref "T5")
      (value "PIC-OUT")
      (footprint "eagle-import:TEMP-PAD")
      (libsource (lib "eagle-import") (part "PIC-OUT"))
    )
    (comp (ref "T7")
      (value "PIC-OUT")
      (footprint "eagle-import:TEMP-PAD")
      (libsource (lib "eagle-import") (part "PIC-OUT"))
    )
    (comp (ref "T13")
      (value "PIC-RPX")
      (footprint "eagle-import:TEMP-PAD")
      (libsource (lib "eagle-import") (part "PIC-RPX"))
    )
    (comp (ref "T14")
      (value "PIC-RPX")
      (footprint "eagle-import:TEMP-PAD")
      (libsource (lib "eagle-import") (part "PIC-RPX"))
    )
    (comp (ref "T15")
      (value "PIC-OUT")
      (footprint "eagle-import:TEMP-PAD")
      (libsource (lib "eagle-import") (part "PIC-OUT"))
    )
    (comp (ref "T27")
      (value "PIC-OUT")
      (footprint "eagle-import:TEMP-PAD")
      (libsource (lib "eagle-import") (part "PIC-OUT"))
    )
    (comp (ref "T32")
      (value "PIC-OUT")
      (footprint "eagle-import:TEMP-PAD")
      (libsource (lib "eagle-import") (part "PIC-OUT"))
    )
    (comp (ref "T33")
      (value "PIC-OUT")
      (footprint "eagle-import:TEMP-PAD")
      (libsource (lib "eagle-import") (part "PIC-OUT"))
    )
    (comp (ref "T36")
      (value "PIC-OUT")
      (footprint "eagle-import:TEMP-PAD")
      (libsource (lib "eagle-import") (part "PIC-OUT"))
    )
    (comp (ref "T37")
      (value "PIN-AN")
      (footprint "eagle-import:TEMP-PAD")
      (libsource (lib "eagle-import") (part "PIN-AN"))
    )
    (comp (ref "T38")
      (value "PIN-AN")
      (footprint "eagle-import:TEMP-PAD")
      (libsource (lib "eagle-import") (part "PIN-AN"))
    )
    (comp (ref "T39")
      (value "PIN-AN")
      (footprint "eagle-import:TEMP-PAD")
      (libsource (lib "eagle-import") (part "PIN-AN"))
    )
    (comp (ref "T45")
      (value "PIC-RPX")
      (footprint "eagle-import:TEMP-PAD")
      (libsource (lib "eagle-import") (part "PIC-RPX"))
    )
    (comp (ref "TP1")
      (value "DNP-TestPoint")
      (footprint "eagle-import:SMD_ROUND_1MM")
      (libsource (lib "eagle-import") (part "ROUND_SMD1MM"))
    )
    (comp (ref "TP2")
      (value "DNP-TestPoint")
      (footprint "eagle-import:TH_ROUND_14MM08MM")
      (libsource (lib "eagle-import") (part "ROUND_SMDTH1.4MM"))
    )
    (comp (ref "TP4")
      (value "DNP-TestPoint")
      (footprint "eagle-import:TH_ROUND_14MM08MM")
      (libsource (lib "eagle-import") (part "ROUND_SMDTH1.4MM"))
    )
    (comp (ref "X1")
      (value "8MHz-5x3.2mm")
      (footprint "eagle-import:7B")
      (libsource (lib "eagle-import") (part "XTAL-7B"))
    )
  )
  (nets
    (net (code "1") (name "+3.3V") (class "Default")
      (node (ref "C47") (pin "1") (pinfunction "1_1") (pintype "passive"))
      (node (ref "C48") (pin "1") (pinfunction "1_1") (pintype "passive"))
      (node (ref "C49") (pin "1") (pinfunction "1_1") (pintype "passive"))
      (node (ref "C50") (pin "1") (pinfunction "1_1") (pintype "passive"))
      (node (ref "C51") (pin "1") (pinfunction "1_1") (pintype "passive"))
      (node (ref "C52") (pin "1") (pinfunction "1_1") (pintype "passive"))
      (node (ref "C69") (pin "1") (pinfunction "1_1") (pintype "passive"))
      (node (ref "C70") (pin "1") (pinfunction "1_1") (pintype "passive"))
      (node (ref "C81") (pin "+") (pinfunction "+_+") (pintype "passive"))
      (node (ref "IC1") (pin "16") (pinfunction "VDD3_16") (pintype "input"))
      (node (ref "IC1") (pin "2") (pinfunction "VDD2_2") (pintype "input"))
      (node (ref "IC1") (pin "37") (pinfunction "VDD4_37") (pintype "input"))
      (node (ref "IC1") (pin "46") (pinfunction "VDD5_46") (pintype "input"))
      (node (ref "IC1") (pin "55") (pinfunction "VUSB3V3_55") (pintype "input"))
      (node (ref "IC1") (pin "62") (pinfunction "VDD6_62") (pintype "input"))
      (node (ref "IC1") (pin "86") (pinfunction "VDD1_86") (pintype "input"))
      (node (ref "J17") (pin "2") (pinfunction "2_2") (pintype "passive"))
      (node (ref "L13") (pin "1") (pinfunction "1_1") (pintype "passive"))
      (node (ref "R103") (pin "2") (pinfunction "2_2") (pintype "passive"))
      (node (ref "R105") (pin "2") (pinfunction "2_2") (pintype "passive"))
      (node (ref "R106") (pin "2") (pinfunction "2_2") (pintype "passive"))
      (node (ref "R129") (pin "1") (pinfunction "1_1") (pintype "passive"))
      (node (ref "R28") (pin "2") (pinfunction "2_2") (pintype "passive"))
      (node (ref "R65") (pin "1") (pinfunction "1_1") (pintype "passive"))
      (node (ref "R82") (pin "1") (pinfunction "1_1") (pintype "passive"))
      (node (ref "R91") (pin "2") (pinfunction "2_2") (pintype "passive"))
    )
    (net (code "2") (name "+3.3V{slash}1") (class "Default")
      (node (ref "C27") (pin "1") (pinfunction "1_1") (pintype "passive"))
      (node (ref "C28") (pin "1") (pinfunction "1_1") (pintype "passive"))
      (node (ref "IC11") (pin "2") (pinfunction "A1_2") (pintype "input"))
      (node (ref "IC11") (pin "8") (pinfunction "VCC_8") (pintype "input"))
      (node (ref "IC7") (pin "8") (pinfunction "VCC_8") (pintype "input"))
      (node (ref "IC9") (pin "3") (pinfunction "/WP_3") (pintype "input"))
      (node (ref "IC9") (pin "7") (pinfunction "/HOLD_7") (pintype "input"))
      (node (ref "IC9") (pin "8") (pinfunction "VCC_8") (pintype "input"))
      (node (ref "Q2") (pin "3") (pinfunction "D_3") (pintype "passive"))
      (node (ref "Q2") (pin "P2") (pinfunction "D1_P2") (pintype "passive"))
      (node (ref "R18") (pin "1") (pinfunction "1_1") (pintype "passive"))
      (node (ref "R25") (pin "2") (pinfunction "2_2") (pintype "passive"))
      (node (ref "R26") (pin "1") (pinfunction "1_1") (pintype "passive"))
      (node (ref "R27") (pin "1") (pinfunction "1_1") (pintype "passive"))
    )
    (net (code "3") (name "+3.3V{slash}2") (class "Default")
      (node (ref "C41") (pin "1") (pinfunction "1_1") (pintype "passive"))
      (node (ref "C86") (pin "+") (pinfunction "+_+") (pintype "passive"))
      (node (ref "IC12") (pin "8") (pinfunction "VCC_8") (pintype "input"))
      (node (ref "Q1") (pin "3") (pinfunction "D_3") (pintype "passive"))
      (node (ref "Q1") (pin "P2") (pinfunction "D1_P2") (pintype "passive"))
      (node (ref "R30") (pin "2") (pinfunction "2_2") (pintype "passive"))
      (node (ref "R34") (pin "1") (pinfunction "1_1") (pintype "passive"))
      (node (ref "R72") (pin "1") (pinfunction "1_1") (pintype "passive"))
      (node (ref "R73") (pin "2") (pinfunction "2_2") (pintype "passive"))
    )
    (net (code "4") (name "/A+") (class "Default")
      (node (ref "IC14") (pin "3") (pinfunction "3_3") (pintype "passive"))
      (node (ref "J3") (pin "4") (pinfunction "4_4") (pintype "passive"))
      (node (ref "J4") (pin "4") (pinfunction "4_4") (pintype "passive"))
      (node (ref "L8") (pin "2") (pinfunction "2_2") (pintype "passive"))
    )
    (net (code "5") (name "/A++") (class "Default")
      (node (ref "IC12") (pin "6") (pinfunction "A_6") (pintype "bidirectional"))
      (node (ref "L8") (pin "1") (pinfunction "1_1") (pintype "passive"))
      (node (ref "R32") (pin "2") (pinfunction "2_2") (pintype "passive"))
      (node (ref "R34") (pin "2") (pinfunction "2_2") (pintype "passive"))
    )
    (net (code "6") (name "/B-") (class "Default")
      (node (ref "IC14") (pin "2") (pinfunction "2_2") (pintype "passive"))
      (node (ref "J3") (pin "5") (pinfunction "5_5") (pintype "passive"))
      (node (ref "J4") (pin "5") (pinfunction "5_5") (pintype "passive"))
      (node (ref "L7") (pin "2") (pinfunction "2_2") (pintype "passive"))
    )
    (net (code "7") (name "/B--") (class "Default")
      (node (ref "IC12") (pin "7") (pinfunction "B_7") (pintype "bidirectional"))
      (node (ref "L7") (pin "1") (pinfunction "1_1") (pintype "passive"))
      (node (ref "R31") (pin "1") (pinfunction "1_1") (pintype "passive"))
      (node (ref "R32") (pin "1") (pinfunction "1_1") (pintype "passive"))
    )
    (net (code "8") (name "/CURR-SENSE") (class "Default")
      (node (ref "C66") (pin "1") (pinfunction "1_1") (pintype "passive"))
      (node (ref "IC1") (pin "14") (pinfunction "AN19/C2INC/RPG9/PMA2/RG9_14") (pintype "bidirectional"))
      (node (ref "O8") (pin "P$1") (pinfunction "TP_P$1") (pintype "passive"))
      (node (ref "R102") (pin "2") (pinfunction "2_2") (pintype "passive"))
      (node (ref "T39") (pin "P$1") (pinfunction "TP_P$1") (pintype "passive"))
    )
    (net (code "9") (name "/D+") (class "Default")
      (node (ref "IC1") (pin "57") (pinfunction "D+/RG2_57") (pintype "bidirectional"))
      (node (ref "IC15") (pin "3") (pinfunction "3_3") (pintype "passive"))
      (node (ref "J12") (pin "3_D+") (pinfunction "D+_3_D+") (pintype "bidirectional"))
    )
    (net (code "10") (name "/D-") (class "Default")
      (node (ref "IC1") (pin "56") (pinfunction "D-/RG3_56") (pintype "bidirectional"))
      (node (ref "IC15") (pin "2") (pinfunction "2_2") (pintype "passive"))
      (node (ref "J12") (pin "2_D-") (pinfunction "D-_2_D-") (pintype "bidirectional"))
    )
    (net (code "11") (name "/LAN-CTL") (class "Default")
      (node (ref "IC1") (pin "84") (pinfunction "PMD15/RD7_84") (pintype "bidirectional"))
      (node (ref "IC12") (pin "2") (pinfunction "/RE_2") (pintype "input"))
      (node (ref "IC12") (pin "3") (pinfunction "DE_3") (pintype "input"))
      (node (ref "O31") (pin "P$1") (pinfunction "TP_P$1") (pintype "passive"))
      (node (ref "R71") (pin "1") (pinfunction "1_1") (pintype "passive"))
      (node (ref "T15") (pin "P$1") (pinfunction "TP_P$1") (pintype "passive"))
    )
    (net (code "12") (name "/LAN-RX") (class "Default")
      (node (ref "IC1") (pin "88") (pinfunction "RPF1/PMD10/RF1_88") (pintype "bidirectional"))
      (node (ref "IC12") (pin "1") (pinfunction "R_1") (pintype "output"))
      (node (ref "O29") (pin "P$1") (pinfunction "TP_P$1") (pintype "passive"))
      (node (ref "R72") (pin "2") (pinfunction "2_2") (pintype "passive"))
      (node (ref "T13") (pin "P$1") (pinfunction "TP_P$1") (pintype "passive"))
    )
    (net (code "13") (name "/LAN-TX") (class "Default")
      (node (ref "IC1") (pin "87") (pinfunction "RPF0/PMD11/RF0_87") (pintype "bidirectional"))
      (node (ref "IC12") (pin "4") (pinfunction "D_4") (pintype "input"))
      (node (ref "O30") (pin "P$1") (pinfunction "TP_P$1") (pintype "passive"))
      (node (ref "R73") (pin "1") (pinfunction "1_1") (pintype "passive"))
      (node (ref "T14") (pin "P$1") (pinfunction "TP_P$1") (pintype "passive"))
    )
    (net (code "14") (name "/LED-PIC") (class "Default")
      (node (ref "IC1") (pin "1") (pinfunction "RG15_1") (pintype "bidirectional"))
      (node (ref "O1") (pin "P$1") (pinfunction "TP_P$1") (pintype "passive"))
      (node (ref "R29") (pin "1") (pinfunction "1_1") (pintype "passive"))
      (node (ref "T36") (pin "P$1") (pinfunction "TP_P$1") (pintype "passive"))
      (node (ref "TP4") (pin "P$1") (pinfunction "TP_P$1") (pintype "passive"))
    )
    (net (code "15") (name "/PGC") (class "Default")
      (node (ref "IC1") (pin "24") (pinfunction "PGEC1/AN1/RPB1/CTED12/RB1_24") (pintype "bidirectional"))
      (node (ref "J17") (pin "5") (pinfunction "5_5") (pintype "passive"))
    )
    (net (code "16") (name "/PGD") (class "Default")
      (node (ref "IC1") (pin "25") (pinfunction "PGED1/AN0/RPB0/RB0_25") (pintype "bidirectional"))
      (node (ref "J17") (pin "4") (pinfunction "4_4") (pintype "passive"))
      (node (ref "R130") (pin "2") (pinfunction "2_2") (pintype "passive"))
    )
    (net (code "17") (name "/POWER-GOOD") (class "Default")
      (node (ref "IC6") (pin "4") (pinfunction "OUT_4") (pintype "output"))
      (node (ref "R130") (pin "1") (pinfunction "1_1") (pintype "passive"))
      (node (ref "T45") (pin "P$1") (pinfunction "TP_P$1") (pintype "passive"))
      (node (ref "TP2") (pin "P$1") (pinfunction "TP_P$1") (pintype "passive"))
    )
    (net (code "18") (name "/REF-EN") (class "Default")
      (node (ref "IC1") (pin "28") (pinfunction "VREF-/CVREF-/PMA7/RA9_28") (pintype "bidirectional"))
      (node (ref "R93") (pin "1") (pinfunction "1_1") (pintype "passive"))
    )
    (net (code "19") (name "/REF2,5V") (class "Default")
      (node (ref "C57") (pin "1") (pinfunction "1_1") (pintype "passive"))
      (node (ref "IC1") (pin "29") (pinfunction "VREF+/CVREF+/PMA6/RA10_29") (pintype "bidirectional"))
      (node (ref "IC13") (pin "2") (pinfunction "VOUT_2") (pintype "bidirectional"))
    )
    (net (code "20") (name "/SCL1-EEPROM") (class "Default")
      (node (ref "IC1") (pin "66") (pinfunction "SCL1/RPA14/RA14_66") (pintype "bidirectional"))
      (node (ref "IC11") (pin "6") (pinfunction "SCL_6") (pintype "input"))
      (node (ref "IC7") (pin "6") (pinfunction "SCL_6") (pintype "input"))
      (node (ref "R26") (pin "2") (pinfunction "2_2") (pintype "passive"))
    )
    (net (code "21") (name "/SCLK2-SPI") (class "Default")
      (node (ref "IC1") (pin "10") (pinfunction "AN16/C1IND/RPG6/SCK2/PMA5/RG6_10") (pintype "bidirectional"))
      (node (ref "IC9") (pin "6") (pinfunction "C_6") (pintype "input"))
    )
    (net (code "22") (name "/SD-CS") (class "Default")
      (node (ref "IC1") (pin "9") (pinfunction "RPC4/CTED7/RC4_9") (pintype "bidirectional"))
      (node (ref "O5") (pin "P$1") (pinfunction "TP_P$1") (pintype "passive"))
    )
    (net (code "23") (name "/SDA1-EEPROM") (class "Default")
      (node (ref "IC1") (pin "67") (pinfunction "SDA1/RPA15/RA15_67") (pintype "bidirectional"))
      (node (ref "IC11") (pin "5") (pinfunction "SDA_5") (pintype "bidirectional"))
      (node (ref "IC7") (pin "5") (pinfunction "SDA_5") (pintype "bidirectional"))
      (node (ref "R27") (pin "2") (pinfunction "2_2") (pintype "passive"))
    )
    (net (code "24") (name "/SDI2-MISO") (class "Default")
      (node (ref "IC1") (pin "22") (pinfunction "PGED3/AN3/C2INA/RPB3/RB3_22") (pintype "bidirectional"))
      (node (ref "IC9") (pin "2") (pinfunction "Q_2") (pintype "bidirectional"))
      (node (ref "O13") (pin "P$1") (pinfunction "TP_P$1") (pintype "passive"))
    )
    (net (code "25") (name "/SDO2-MOSI") (class "Default")
      (node (ref "IC1") (pin "20") (pinfunction "AN5/C1INA/RPB5/RB5_20") (pintype "bidirectional"))
      (node (ref "IC9") (pin "5") (pinfunction "D_5") (pintype "input"))
      (node (ref "O12") (pin "P$1") (pinfunction "TP_P$1") (pintype "passive"))
    )
    (net (code "26") (name "/VBAT-LAN") (class "Default")
      (node (ref "D3") (pin "C") (pinfunction "C_C") (pintype "passive"))
      (node (ref "J3") (pin "1") (pinfunction "1_1") (pintype "passive"))
      (node (ref "J3") (pin "3") (pinfunction "3_3") (pintype "passive"))
      (node (ref "J4") (pin "1") (pinfunction "1_1") (pintype "passive"))
      (node (ref "J4") (pin "3") (pinfunction "3_3") (pintype "passive"))
      (node (ref "L11") (pin "2") (pinfunction "2_2") (pintype "passive"))
    )
    (net (code "27") (name "/VBAT-LAN-F") (class "Default")
      (node (ref "C33") (pin "1") (pinfunction "1_1") (pintype "passive"))
      (node (ref "C34") (pin "1") (pinfunction "1_1") (pintype "passive"))
      (node (ref "D6") (pin "K") (pinfunction "K_K") (pintype "passive"))
      (node (ref "L11") (pin "1") (pinfunction "1_1") (pintype "passive"))
      (node (ref "Q5") (pin "2") (pinfunction "S_2") (pintype "passive"))
      (node (ref "Q5") (pin "5") (pinfunction "S_5") (pintype "passive"))
      (node (ref "R132") (pin "1") (pinfunction "1_1") (pintype "passive"))
      (node (ref "R36") (pin "2") (pinfunction "2_2") (pintype "passive"))
      (node (ref "R38") (pin "2") (pinfunction "2_2") (pintype "passive"))
      (node (ref "R42") (pin "1") (pinfunction "1_1") (pintype "passive"))
      (node (ref "R45") (pin "1") (pinfunction "1_1") (pintype "passive"))
      (node (ref "R94") (pin "1") (pinfunction "1_1") (pintype "passive"))
    )
    (net (code "28") (name "/VBAT-ON") (class "Default")
      (node (ref "IC1") (pin "52") (pinfunction "RPF2/RF2_52") (pintype "bidirectional"))
      (node (ref "O42") (pin "P$1") (pinfunction "TP_P$1") (pintype "passive"))
      (node (ref "Q4") (pin "2") (pinfunction "G_2") (pintype "passive"))
      (node (ref "R132") (pin "2") (pinfunction "2_2") (pintype "passive"))
      (node (ref "R41") (pin "1") (pinfunction "1_1") (pintype "passive"))
      (node (ref "T5") (pin "P$1") (pinfunction "TP_P$1") (pintype "passive"))
    )
    (net (code "29") (name "/VBAT-SENSE") (class "Default")
      (node (ref "C64") (pin "1") (pinfunction "1_1") (pintype "passive"))
      (node (ref "IC1") (pin "26") (pinfunction "PGEC2/AN6/RPB6/RB6_26") (pintype "bidirectional"))
      (node (ref "O15") (pin "P$1") (pinfunction "TP_P$1") (pintype "passive"))
      (node (ref "R100") (pin "1") (pinfunction "1_1") (pintype "passive"))
      (node (ref "T37") (pin "P$1") (pinfunction "TP_P$1") (pintype "passive"))
    )
    (net (code "30") (name "/VBATLAN-SENSE") (class "Default")
      (node (ref "C36") (pin "1") (pinfunction "1_1") (pintype "passive"))
      (node (ref "IC1") (pin "27") (pinfunction "PGED2/AN7/RPB7/CTED3/RB7_27") (pintype "bidirectional"))
      (node (ref "O16") (pin "P$1") (pinfunction "TP_P$1") (pintype "passive"))
      (node (ref "R101") (pin "1") (pinfunction "1_1") (pintype "passive"))
      (node (ref "T38") (pin "P$1") (pinfunction "TP_P$1") (pintype "passive"))
    )
    (net (code "31") (name "/VBUS") (class "Default")
      (node (ref "IC1") (pin "54") (pinfunction "VBUS_54") (pintype "input"))
      (node (ref "R128") (pin "2") (pinfunction "2_2") (pintype "passive"))
    )
    (net (code "32") (name "/VPS-ON") (class "Default")
      (node (ref "IC1") (pin "53") (pinfunction "RPF8/RF8_53") (pintype "bidirectional"))
      (node (ref "O41") (pin "P$1") (pinfunction "TP_P$1") (pintype "passive"))
      (node (ref "Q4") (pin "5") (pinfunction "G_5") (pintype "passive"))
      (node (ref "R44") (pin "1") (pinfunction "1_1") (pintype "passive"))
      (node (ref "T7") (pin "P$1") (pinfunction "TP_P$1") (pintype "passive"))
    )
    (net (code "33") (name "/VPS-PWR") (class "Default")
      (node (ref "D4") (pin "C") (pinfunction "C_C") (pintype "passive"))
      (node (ref "J3") (pin "6") (pinfunction "6_6") (pintype "passive"))
      (node (ref "J4") (pin "6") (pinfunction "6_6") (pintype "passive"))
      (node (ref "L10") (pin "2") (pinfunction "2_2") (pintype "passive"))
    )
    (net (code "34") (name "/VPS-PWR-F") (class "Default")
      (node (ref "L10") (pin "1") (pinfunction "1_1") (pintype "passive"))
      (node (ref "Q5") (pin "4") (pinfunction "D_4") (pintype "passive"))
      (node (ref "R23") (pin "2") (pinfunction "2_2") (pintype "passive"))
    )
    (net (code "35") (name "/VPS-SENSE") (class "Default")
      (node (ref "C65") (pin "1") (pinfunction "1_1") (pintype "passive"))
      (node (ref "IC1") (pin "12") (pinfunction "AN18/C2IND/RPG8/PMA3/RG8_12") (pintype "bidirectional"))
      (node (ref "O7") (pin "P$1") (pinfunction "TP_P$1") (pintype "passive"))
      (node (ref "R48") (pin "2") (pinfunction "2_2") (pintype "passive"))
      (node (ref "R49") (pin "1") (pinfunction "1_1") (pintype "passive"))
      (node (ref "T3") (pin "P$1") (pinfunction "TP_P$1") (pintype "passive"))
    )
    (net (code "36") (name "/{slash}3.3V1PWRON") (class "Default")
      (node (ref "IC1") (pin "21") (pinfunction "AN4/C1INB/USBOEN/RB4_21") (pintype "bidirectional"))
      (node (ref "O44") (pin "P$1") (pinfunction "TP_P$1") (pintype "passive"))
      (node (ref "R24") (pin "2") (pinfunction "2_2") (pintype "passive"))
      (node (ref "T32") (pin "P$1") (pinfunction "TP_P$1") (pintype "passive"))
    )
    (net (code "37") (name "/{slash}3.3V2PWRON") (class "Default")
      (node (ref "IC1") (pin "96") (pinfunction "TRD1/RG12_96") (pintype "bidirectional"))
      (node (ref "O23") (pin "P$1") (pinfunction "TP_P$1") (pintype "passive"))
      (node (ref "R75") (pin "2") (pinfunction "2_2") (pintype "passive"))
      (node (ref "T33") (pin "P$1") (pinfunction "TP_P$1") (pintype "passive"))
    )
    (net (code "38") (name "/{slash}FMEM1-CS") (class "Default")
      (node (ref "IC1") (pin "11") (pinfunction "AN17/C1INC/RPG7/PMA4/RG7_11") (pintype "bidirectional"))
      (node (ref "IC9") (pin "1") (pinfunction "/S_1") (pintype "input"))
      (node (ref "O6") (pin "P$1") (pinfunction "TP_P$1") (pintype "passive"))
      (node (ref "R25") (pin "1") (pinfunction "1_1") (pintype "passive"))
      (node (ref "T27") (pin "P$1") (pinfunction "TP_P$1") (pintype "passive"))
    )
    (net (code "39") (name "/{slash}MCLR") (class "Default")
      (node (ref "IC1") (pin "13") (pinfunction "~{MCLR}_13") (pintype "input"))
      (node (ref "J17") (pin "1") (pinfunction "1_1") (pintype "passive"))
      (node (ref "R90") (pin "2") (pinfunction "2_2") (pintype "passive"))
    )
    (net (code "40") (name "DGND") (class "Default")
      (node (ref "C22") (pin "2") (pinfunction "2_2") (pintype "passive"))
      (node (ref "C23") (pin "2") (pinfunction "2_2") (pintype "passive"))
      (node (ref "C24") (pin "1") (pinfunction "1_1") (pintype "passive"))
      (node (ref "C27") (pin "2") (pinfunction "2_2") (pintype "passive"))
      (node (ref "C28") (pin "2") (pinfunction "2_2") (pintype "passive"))
      (node (ref "C29") (pin "2") (pinfunction "2_2") (pintype "passive"))
      (node (ref "C30") (pin "2") (pinfunction "2_2") (pintype "passive"))
      (node (ref "C31") (pin "-") (pinfunction "-_-") (pintype "passive"))
      (node (ref "C35") (pin "2") (pinfunction "2_2") (pintype "passive"))
      (node (ref "C36") (pin "2") (pinfunction "2_2") (pintype "passive"))
      (node (ref "C40") (pin "2") (pinfunction "2_2") (pintype "passive"))
      (node (ref "C41") (pin "2") (pinfunction "2_2") (pintype "passive"))
      (node (ref "C47") (pin "2") (pinfunction "2_2") (pintype "passive"))
      (node (ref "C48") (pin "2") (pinfunction "2_2") (pintype "passive"))
      (node (ref "C49") (pin "2") (pinfunction "2_2") (pintype "passive"))
      (node (ref "C50") (pin "2") (pinfunction "2_2") (pintype "passive"))
      (node (ref "C51") (pin "2") (pinfunction "2_2") (pintype "passive"))
      (node (ref "C52") (pin "2") (pinfunction "2_2") (pintype "passive"))
      (node (ref "C53") (pin "2") (pinfunction "2_2") (pintype "passive"))
      (node (ref "C54") (pin "-") (pinfunction "-_-") (pintype "passive"))
      (node (ref "C55") (pin "2") (pinfunction "2_2") (pintype "passive"))
      (node (ref "C56") (pin "-") (pinfunction "-_-") (pintype "passive"))
      (node (ref "C57") (pin "2") (pinfunction "2_2") (pintype "passive"))
      (node (ref "C58") (pin "2") (pinfunction "2_2") (pintype "passive"))
      (node (ref "C59") (pin "2") (pinfunction "2_2") (pintype "passive"))
      (node (ref "C60") (pin "2") (pinfunction "2_2") (pintype "passive"))
      (node (ref "C61") (pin "2") (pinfunction "2_2") (pintype "passive"))
      (node (ref "C62") (pin "2") (pinfunction "2_2") (pintype "passive"))
      (node (ref "C63") (pin "2") (pinfunction "2_2") (pintype "passive"))
      (node (ref "C64") (pin "2") (pinfunction "2_2") (pintype "passive"))
      (node (ref "C65") (pin "2") (pinfunction "2_2") (pintype "passive"))
      (node (ref "C66") (pin "2") (pinfunction "2_2") (pintype "passive"))
      (node (ref "C67") (pin "2") (pinfunction "2_2") (pintype "passive"))
      (node (ref "C81") (pin "-") (pinfunction "-_-") (pintype "passive"))
      (node (ref "C83") (pin "2") (pinfunction "2_2") (pintype "passive"))
      (node (ref "C84") (pin "2") (pinfunction "2_2") (pintype "passive"))
      (node (ref "C85") (pin "2") (pinfunction "2_2") (pintype "passive"))
      (node (ref "C86") (pin "-") (pinfunction "-_-") (pintype "passive"))
      (node (ref "C88") (pin "2") (pinfunction "2_2") (pintype "passive"))
      (node (ref "D2") (pin "-") (pinfunction "A_-") (pintype "passive"))
      (node (ref "D5") (pin "K") (pinfunction "K_K") (pintype "passive"))
      (node (ref "D7") (pin "A") (pinfunction "A_A") (pintype "passive"))
      (node (ref "IC1") (pin "15") (pinfunction "VSS2_15") (pintype "input"))
      (node (ref "IC1") (pin "31") (pinfunction "AVSS_31") (pintype "input"))
      (node (ref "IC1") (pin "36") (pinfunction "VSS3_36") (pintype "input"))
      (node (ref "IC1") (pin "45") (pinfunction "VSS4_45") (pintype "input"))
      (node (ref "IC1") (pin "65") (pinfunction "VSS5_65") (pintype "input"))
      (node (ref "IC1") (pin "75") (pinfunction "VSS1_75") (pintype "input"))
      (node (ref "IC10") (pin "1") (pinfunction "GND_1") (pintype "input"))
      (node (ref "IC10") (pin "2") (pinfunction "GND1_2") (pintype "input"))
      (node (ref "IC11") (pin "1") (pinfunction "A0_1") (pintype "input"))
      (node (ref "IC11") (pin "3") (pinfunction "A2_3") (pintype "input"))
      (node (ref "IC11") (pin "4") (pinfunction "GND_4") (pintype "input"))
      (node (ref "IC12") (pin "5") (pinfunction "GND_5") (pintype "input"))
      (node (ref "IC13") (pin "3") (pinfunction "GND_3") (pintype "bidirectional"))
      (node (ref "IC15") (pin "1") (pinfunction "1_1") (pintype "input"))
      (node (ref "IC16") (pin "4") (pinfunction "V-_4") (pintype "input"))
      (node (ref "IC6") (pin "2") (pinfunction "GND_2") (pintype "input"))
      (node (ref "IC7") (pin "1") (pinfunction "A0_1") (pintype "input"))
      (node (ref "IC7") (pin "2") (pinfunction "A1_2") (pintype "input"))
      (node (ref "IC7") (pin "3") (pinfunction "A2_3") (pintype "input"))
      (node (ref "IC7") (pin "4") (pinfunction "GND_4") (pintype "input"))
      (node (ref "IC7") (pin "7") (pinfunction "WP_7") (pintype "input"))
      (node (ref "IC8") (pin "10") (pinfunction "SYNC_10") (pintype "bidirectional"))
      (node (ref "IC8") (pin "EP") (pinfunction "GND_EP") (pintype "bidirectional"))
      (node (ref "IC9") (pin "4") (pinfunction "GND_4") (pintype "input"))
      (node (ref "J12") (pin "4_GND") (pinfunction "GND_4_GND") (pintype "bidirectional"))
      (node (ref "J12") (pin "SH1") (pinfunction "GND_SH1_SH1") (pintype "bidirectional"))
      (node (ref "J12") (pin "SH2") (pinfunction "GND_SH2_SH2") (pintype "bidirectional"))
      (node (ref "J17") (pin "3") (pinfunction "3_3") (pintype "passive"))
      (node (ref "L12") (pin "1") (pinfunction "1_1") (pintype "passive"))
      (node (ref "PCB1") (pin "PAD_GND_1") (pinfunction "PAD_GND_1_PAD_GND_1") (pintype "bidirectional"))
      (node (ref "PCB1") (pin "PAD_GND_2") (pinfunction "PAD_GND_2_PAD_GND_2") (pintype "bidirectional"))
      (node (ref "PCB1") (pin "PAD_GND_3") (pinfunction "PAD_GND_3_PAD_GND_3") (pintype "bidirectional"))
      (node (ref "PCB1") (pin "PAD_GND_4") (pinfunction "PAD_GND_4_PAD_GND_4") (pintype "bidirectional"))
      (node (ref "R17") (pin "2") (pinfunction "2_2") (pintype "passive"))
      (node (ref "R19") (pin "2") (pinfunction "2_2") (pintype "passive"))
      (node (ref "R21") (pin "2") (pinfunction "2_2") (pintype "passive"))
      (node (ref "R31") (pin "2") (pinfunction "2_2") (pintype "passive"))
      (node (ref "R40") (pin "1") (pinfunction "1_1") (pintype "passive"))
      (node (ref "R41") (pin "2") (pinfunction "2_2") (pintype "passive"))
      (node (ref "R43") (pin "1") (pinfunction "1_1") (pintype "passive"))
      (node (ref "R44") (pin "2") (pinfunction "2_2") (pintype "passive"))
      (node (ref "R46") (pin "1") (pinfunction "1_1") (pintype "passive"))
      (node (ref "R48") (pin "1") (pinfunction "1_1") (pintype "passive"))
      (node (ref "R71") (pin "2") (pinfunction "2_2") (pintype "passive"))
      (node (ref "R96") (pin "2") (pinfunction "2_2") (pintype "passive"))
      (node (ref "R99") (pin "2") (pinfunction "2_2") (pintype "passive"))
    )
    (net (code "41") (name "Net-(C24-Pad2)") (class "Default")
      (node (ref "C24") (pin "2") (pinfunction "2_2") (pintype "passive"))
      (node (ref "R77") (pin "2") (pinfunction "2_2") (pintype "passive"))
    )
    (net (code "42") (name "Net-(C39-Pad1)") (class "Default")
      (node (ref "C39") (pin "1") (pinfunction "1_1") (pintype "passive"))
      (node (ref "IC14") (pin "4") (pinfunction "4_4") (pintype "input"))
      (node (ref "R30") (pin "1") (pinfunction "1_1") (pintype "passive"))
    )
    (net (code "43") (name "Net-(C39-Pad2)") (class "Default")
      (node (ref "C39") (pin "2") (pinfunction "2_2") (pintype "passive"))
      (node (ref "D3") (pin "A") (pinfunction "A_A") (pintype "passive"))
      (node (ref "D4") (pin "A") (pinfunction "A_A") (pintype "passive"))
      (node (ref "IC14") (pin "1") (pinfunction "1_1") (pintype "input"))
      (node (ref "J3") (pin "2") (pinfunction "2_2") (pintype "passive"))
      (node (ref "J3") (pin "7") (pinfunction "7_7") (pintype "passive"))
      (node (ref "J3") (pin "8") (pinfunction "8_8") (pintype "passive"))
      (node (ref "J4") (pin "2") (pinfunction "2_2") (pintype "passive"))
      (node (ref "J4") (pin "7") (pinfunction "7_7") (pintype "passive"))
      (node (ref "J4") (pin "8") (pinfunction "8_8") (pintype "passive"))
      (node (ref "L12") (pin "2") (pinfunction "2_2") (pintype "passive"))
    )
    (net (code "44") (name "Net-(C40-Pad1)") (class "Default")
      (node (ref "C40") (pin "1") (pinfunction "1_1") (pintype "passive"))
      (node (ref "R90") (pin "1") (pinfunction "1_1") (pintype "passive"))
      (node (ref "R91") (pin "1") (pinfunction "1_1") (pintype "passive"))
    )
    (net (code "45") (name "Net-(D2-C)") (class "Default")
      (node (ref "C26") (pin "1") (pinfunction "1_1") (pintype "passive"))
      (node (ref "C30") (pin "1") (pinfunction "1_1") (pintype "passive"))
      (node (ref "C31") (pin "+") (pinfunction "+_+") (pintype "passive"))
      (node (ref "D2") (pin "+") (pinfunction "C_+") (pintype "passive"))
      (node (ref "IC8") (pin "1") (pinfunction "BD_1") (pintype "bidirectional"))
      (node (ref "L9") (pin "2") (pinfunction "2_2") (pintype "passive"))
      (node (ref "R129") (pin "2") (pinfunction "2_2") (pintype "passive"))
      (node (ref "R20") (pin "1") (pinfunction "1_1") (pintype "passive"))
    )
    (net (code "46") (name "Net-(D5-PadA)") (class "Default")
      (node (ref "D5") (pin "A") (pinfunction "A_A") (pintype "passive"))
      (node (ref "R29") (pin "2") (pinfunction "2_2") (pintype "passive"))
    )
    (net (code "47") (name "Net-(IC1-AVDD)") (class "Default")
      (node (ref "C55") (pin "1") (pinfunction "1_1") (pintype "passive"))
      (node (ref "C56") (pin "+") (pinfunction "+_+") (pintype "passive"))
      (node (ref "C88") (pin "1") (pinfunction "1_1") (pintype "passive"))
      (node (ref "IC1") (pin "30") (pinfunction "AVDD_30") (pintype "input"))
      (node (ref "R92") (pin "2") (pinfunction "2_2") (pintype "passive"))
    )
    (net (code "48") (name "Net-(IC1-CLKI{slash}RC12{slash}OSC1)") (class "Default")
      (node (ref "C60") (pin "1") (pinfunction "1_1") (pintype "passive"))
      (node (ref "IC1") (pin "63") (pinfunction "CLKI/RC12/OSC1_63") (pintype "bidirectional"))
      (node (ref "X1") (pin "3") (pinfunction "2_3") (pintype "passive"))
    )
    (net (code "49") (name "Net-(IC1-CLKO{slash}RC15{slash}OSC2)") (class "Default")
      (node (ref "C61") (pin "1") (pinfunction "1_1") (pintype "passive"))
      (node (ref "IC1") (pin "64") (pinfunction "CLKO/RC15/OSC2_64") (pintype "bidirectional"))
      (node (ref "X1") (pin "1") (pinfunction "1_1") (pintype "passive"))
    )
    (net (code "50") (name "Net-(IC1-VCAP)") (class "Default")
      (node (ref "C53") (pin "1") (pinfunction "1_1") (pintype "passive"))
      (node (ref "C54") (pin "+") (pinfunction "+_+") (pintype "passive"))
      (node (ref "IC1") (pin "85") (pinfunction "VCAP_85") (pintype "input"))
    )
    (net (code "51") (name "Net-(IC6-HTH)") (class "Default")
      (node (ref "IC6") (pin "1") (pinfunction "HTH_1") (pintype "input"))
      (node (ref "R46") (pin "2") (pinfunction "2_2") (pintype "passive"))
      (node (ref "R47") (pin "1") (pinfunction "1_1") (pintype "passive"))
    )
    (net (code "52") (name "Net-(IC6-LTH)") (class "Default")
      (node (ref "IC6") (pin "3") (pinfunction "LTH_3") (pintype "input"))
      (node (ref "R33") (pin "1") (pinfunction "1_1") (pintype "passive"))
      (node (ref "R47") (pin "2") (pinfunction "2_2") (pintype "passive"))
    )
    (net (code "53") (name "Net-(IC6-VDD)") (class "Default")
      (node (ref "C35") (pin "1") (pinfunction "1_1") (pintype "passive"))
      (node (ref "IC6") (pin "5") (pinfunction "VDD_5") (pintype "input"))
      (node (ref "R28") (pin "1") (pinfunction "1_1") (pintype "passive"))
    )
    (net (code "54") (name "Net-(IC8-BOOST)") (class "Default")
      (node (ref "C25") (pin "2") (pinfunction "2_2") (pintype "passive"))
      (node (ref "IC8") (pin "2") (pinfunction "BOOST_2") (pintype "bidirectional"))
    )
    (net (code "55") (name "Net-(IC8-EN)") (class "Default")
      (node (ref "IC8") (pin "5") (pinfunction "EN_5") (pintype "bidirectional"))
      (node (ref "JP1") (pin "2") (pinfunction "2_2") (pintype "bidirectional"))
      (node (ref "R22") (pin "2") (pinfunction "2_2") (pintype "passive"))
    )
    (net (code "56") (name "Net-(IC8-FB)") (class "Default")
      (node (ref "C26") (pin "2") (pinfunction "2_2") (pintype "passive"))
      (node (ref "IC8") (pin "6") (pinfunction "FB_6") (pintype "bidirectional"))
      (node (ref "R19") (pin "1") (pinfunction "1_1") (pintype "passive"))
      (node (ref "R20") (pin "2") (pinfunction "2_2") (pintype "passive"))
    )
    (net (code "57") (name "Net-(IC8-RT)") (class "Default")
      (node (ref "IC8") (pin "8") (pinfunction "RT_8") (pintype "bidirectional"))
      (node (ref "R17") (pin "1") (pinfunction "1_1") (pintype "passive"))
    )
    (net (code "58") (name "Net-(IC8-SS)") (class "Default")
      (node (ref "IC8") (pin "7") (pinfunction "SS_7") (pintype "bidirectional"))
      (node (ref "R77") (pin "1") (pinfunction "1_1") (pintype "passive"))
    )
    (net (code "59") (name "Net-(IC8-SW)") (class "Default")
      (node (ref "C25") (pin "1") (pinfunction "1_1") (pintype "passive"))
      (node (ref "D7") (pin "K") (pinfunction "K_K") (pintype "passive"))
      (node (ref "IC8") (pin "3") (pinfunction "SW_3") (pintype "bidirectional"))
      (node (ref "L9") (pin "1") (pinfunction "1_1") (pintype "passive"))
    )
    (net (code "60") (name "Net-(IC10-OUT)") (class "Default")
      (node (ref "IC10") (pin "3") (pinfunction "OUT_3") (pintype "output"))
      (node (ref "R102") (pin "1") (pinfunction "1_1") (pintype "passive"))
    )
    (net (code "61") (name "Net-(IC10-VIN+)") (class "Default")
      (node (ref "C29") (pin "1") (pinfunction "1_1") (pintype "passive"))
      (node (ref "F1") (pin "1") (pinfunction "1_1") (pintype "passive"))
      (node (ref "IC10") (pin "5") (pinfunction "VIN+_5") (pintype "input"))
      (node (ref "R39") (pin "2") (pinfunction "2_2") (pintype "passive"))
    )
    (net (code "62") (name "Net-(IC11-WP)") (class "Default")
      (node (ref "IC11") (pin "7") (pinfunction "WP_7") (pintype "input"))
      (node (ref "R18") (pin "2") (pinfunction "2_2") (pintype "passive"))
      (node (ref "TP1") (pin "P$1") (pinfunction "TP_P$1") (pintype "passive"))
    )
    (net (code "63") (name "Net-(IC13-VIN)") (class "Default")
      (node (ref "C58") (pin "1") (pinfunction "1_1") (pintype "passive"))
      (node (ref "C59") (pin "1") (pinfunction "1_1") (pintype "passive"))
      (node (ref "IC13") (pin "1") (pinfunction "VIN_1") (pintype "bidirectional"))
      (node (ref "R93") (pin "2") (pinfunction "2_2") (pintype "passive"))
    )
    (net (code "64") (name "Net-(IC16A-+IN)") (class "Default")
      (node (ref "C62") (pin "1") (pinfunction "1_1") (pintype "passive"))
      (node (ref "IC16") (pin "3") (pinfunction "+IN_3") (pintype "input"))
      (node (ref "R95") (pin "2") (pinfunction "2_2") (pintype "passive"))
      (node (ref "R96") (pin "1") (pinfunction "1_1") (pintype "passive"))
    )
    (net (code "65") (name "Net-(IC16A--IN)") (class "Default")
      (node (ref "IC16") (pin "1") (pinfunction "OUT_1") (pintype "output"))
      (node (ref "IC16") (pin "2") (pinfunction "-IN_2") (pintype "input"))
      (node (ref "R101") (pin "2") (pinfunction "2_2") (pintype "passive"))
    )
    (net (code "66") (name "Net-(IC16B-+IN)") (class "Default")
      (node (ref "C63") (pin "1") (pinfunction "1_1") (pintype "passive"))
      (node (ref "IC16") (pin "5") (pinfunction "+IN_5") (pintype "input"))
      (node (ref "R98") (pin "2") (pinfunction "2_2") (pintype "passive"))
      (node (ref "R99") (pin "1") (pinfunction "1_1") (pintype "passive"))
    )
    (net (code "67") (name "Net-(IC16B--IN)") (class "Default")
      (node (ref "IC16") (pin "6") (pinfunction "-IN_6") (pintype "input"))
      (node (ref "IC16") (pin "7") (pinfunction "OUT_7") (pintype "output"))
      (node (ref "R100") (pin "2") (pinfunction "2_2") (pintype "passive"))
    )
    (net (code "68") (name "Net-(IC16C-V+)") (class "Default")
      (node (ref "C67") (pin "1") (pinfunction "1_1") (pintype "passive"))
      (node (ref "IC16") (pin "8") (pinfunction "V+_8") (pintype "input"))
      (node (ref "R103") (pin "1") (pinfunction "1_1") (pintype "passive"))
    )
    (net (code "69") (name "Net-(J12-+5V)") (class "Default")
      (node (ref "C85") (pin "1") (pinfunction "1_1") (pintype "passive"))
      (node (ref "D6") (pin "A") (pinfunction "A_A") (pintype "passive"))
      (node (ref "IC15") (pin "4") (pinfunction "4_4") (pintype "input"))
      (node (ref "J12") (pin "1_+5V") (pinfunction "+5V_1_+5V") (pintype "bidirectional"))
      (node (ref "R128") (pin "1") (pinfunction "1_1") (pintype "passive"))
    )
    (net (code "70") (name "Net-(JP1-Pad1)") (class "Default")
      (node (ref "JP1") (pin "1") (pinfunction "1_1") (pintype "bidirectional"))
      (node (ref "R21") (pin "1") (pinfunction "1_1") (pintype "passive"))
    )
    (net (code "71") (name "Net-(L13-Pad2)") (class "Default")
      (node (ref "L13") (pin "2") (pinfunction "2_2") (pintype "passive"))
      (node (ref "R92") (pin "1") (pinfunction "1_1") (pintype "passive"))
    )
    (net (code "72") (name "Net-(Q1B-G)") (class "Default")
      (node (ref "C70") (pin "2") (pinfunction "2_2") (pintype "passive"))
      (node (ref "Q1") (pin "5") (pinfunction "G_5") (pintype "passive"))
      (node (ref "R75") (pin "1") (pinfunction "1_1") (pintype "passive"))
      (node (ref "R82") (pin "2") (pinfunction "2_2") (pintype "passive"))
    )
    (net (code "73") (name "Net-(Q1B-S)") (class "Default")
      (node (ref "Q1") (pin "4") (pinfunction "S_4") (pintype "passive"))
      (node (ref "R106") (pin "1") (pinfunction "1_1") (pintype "passive"))
    )
    (net (code "74") (name "Net-(Q2B-G)") (class "Default")
      (node (ref "C69") (pin "2") (pinfunction "2_2") (pintype "passive"))
      (node (ref "Q2") (pin "5") (pinfunction "G_5") (pintype "passive"))
      (node (ref "R24") (pin "1") (pinfunction "1_1") (pintype "passive"))
      (node (ref "R65") (pin "2") (pinfunction "2_2") (pintype "passive"))
    )
    (net (code "75") (name "Net-(Q2B-S)") (class "Default")
      (node (ref "Q2") (pin "4") (pinfunction "S_4") (pintype "passive"))
      (node (ref "R105") (pin "1") (pinfunction "1_1") (pintype "passive"))
    )
    (net (code "76") (name "Net-(Q4A-D)") (class "Default")
      (node (ref "C33") (pin "2") (pinfunction "2_2") (pintype "passive"))
      (node (ref "Q4") (pin "6") (pinfunction "D_6") (pintype "passive"))
      (node (ref "Q5") (pin "1") (pinfunction "G_1") (pintype "passive"))
      (node (ref "R42") (pin "2") (pinfunction "2_2") (pintype "passive"))
    )
    (net (code "77") (name "Net-(Q4A-S)") (class "Default")
      (node (ref "Q4") (pin "1") (pinfunction "S_1") (pintype "passive"))
      (node (ref "R40") (pin "2") (pinfunction "2_2") (pintype "passive"))
    )
    (net (code "78") (name "Net-(Q4B-D)") (class "Default")
      (node (ref "C34") (pin "2") (pinfunction "2_2") (pintype "passive"))
      (node (ref "Q4") (pin "3") (pinfunction "D_3") (pintype "passive"))
      (node (ref "Q5") (pin "3") (pinfunction "G_3") (pintype "passive"))
      (node (ref "R45") (pin "2") (pinfunction "2_2") (pintype "passive"))
    )
    (net (code "79") (name "Net-(Q4B-S)") (class "Default")
      (node (ref "Q4") (pin "4") (pinfunction "S_4") (pintype "passive"))
      (node (ref "R43") (pin "2") (pinfunction "2_2") (pintype "passive"))
    )
    (net (code "80") (name "Net-(Q5A-D)") (class "Default")
      (node (ref "F1") (pin "2") (pinfunction "2_2") (pintype "passive"))
      (node (ref "Q5") (pin "6") (pinfunction "D_6") (pintype "passive"))
      (node (ref "R35") (pin "1") (pinfunction "1_1") (pintype "passive"))
      (node (ref "R37") (pin "1") (pinfunction "1_1") (pintype "passive"))
      (node (ref "R97") (pin "1") (pinfunction "1_1") (pintype "passive"))
    )
    (net (code "81") (name "Net-(R23-Pad1)") (class "Default")
      (node (ref "R23") (pin "1") (pinfunction "1_1") (pintype "passive"))
      (node (ref "R49") (pin "2") (pinfunction "2_2") (pintype "passive"))
    )
    (net (code "82") (name "Net-(R35-Pad2)") (class "Default")
      (node (ref "R35") (pin "2") (pinfunction "2_2") (pintype "passive"))
      (node (ref "R36") (pin "1") (pinfunction "1_1") (pintype "passive"))
      (node (ref "R37") (pin "2") (pinfunction "2_2") (pintype "passive"))
      (node (ref "R38") (pin "1") (pinfunction "1_1") (pintype "passive"))
    )
    (net (code "83") (name "Net-(R94-Pad2)") (class "Default")
      (node (ref "R94") (pin "2") (pinfunction "2_2") (pintype "passive"))
      (node (ref "R95") (pin "1") (pinfunction "1_1") (pintype "passive"))
    )
    (net (code "84") (name "Net-(R97-Pad2)") (class "Default")
      (node (ref "R97") (pin "2") (pinfunction "2_2") (pintype "passive"))
      (node (ref "R98") (pin "1") (pinfunction "1_1") (pintype "passive"))
    )
    (net (code "85") (name "VBAT") (class "Default")
      (node (ref "C22") (pin "1") (pinfunction "1_1") (pintype "passive"))
      (node (ref "C23") (pin "1") (pinfunction "1_1") (pintype "passive"))
      (node (ref "C83") (pin "1") (pinfunction "1_1") (pintype "passive"))
      (node (ref "C84") (pin "1") (pinfunction "1_1") (pintype "passive"))
      (node (ref "IC10") (pin "4") (pinfunction "VIN-_4") (pintype "input"))
      (node (ref "IC8") (pin "4") (pinfunction "VIN_4") (pintype "bidirectional"))
      (node (ref "JP1") (pin "3") (pinfunction "3_3") (pintype "bidirectional"))
      (node (ref "R22") (pin "1") (pinfunction "1_1") (pintype "passive"))
      (node (ref "R33") (pin "2") (pinfunction "2_2") (pintype "passive"))
      (node (ref "R39") (pin "1") (pinfunction "1_1") (pintype "passive"))
    )
    (net (code "86") (name "unconnected-(IC1-AN8{slash}RPB8{slash}CTED10{slash}RB8-Pad32)") (class "Default")
      (node (ref "IC1") (pin "32") (pinfunction "AN8/RPB8/CTED10/RB8_32") (pintype "bidirectional"))
    )
    (net (code "87") (name "unconnected-(IC1-AN9{slash}RPB9{slash}CTED4{slash}RB9-Pad33)") (class "Default")
      (node (ref "IC1") (pin "33") (pinfunction "AN9/RPB9/CTED4/RB9_33") (pintype "bidirectional"))
    )
    (net (code "88") (name "unconnected-(IC1-AN11{slash}PMA12{slash}RB11-Pad35)") (class "Default")
      (node (ref "IC1") (pin "35") (pinfunction "AN11/PMA12/RB11_35") (pintype "bidirectional"))
    )
    (net (code "89") (name "unconnected-(IC1-AN12{slash}PMA11{slash}RB12-Pad41)") (class "Default")
      (node (ref "IC1") (pin "41") (pinfunction "AN12/PMA11/RB12_41") (pintype "bidirectional"))
    )
    (net (code "90") (name "unconnected-(IC1-AN13{slash}RB13-Pad42)") (class "Default")
      (node (ref "IC1") (pin "42") (pinfunction "AN13/RB13_42") (pintype "bidirectional"))
    )
    (net (code "91") (name "unconnected-(IC1-AN14{slash}RPB14{slash}PMA1{slash}CTED5{slash}RB14-Pad43)") (class "Default")
      (node (ref "IC1") (pin "43") (pinfunction "AN14/RPB14/PMA1/CTED5/RB14_43") (pintype "bidirectional"))
    )
    (net (code "92") (name "unconnected-(IC1-AN15{slash}RPB15{slash}PMA0{slash}CTED6{slash}{slash}RB15-Pad44)") (class "Default")
      (node (ref "IC1") (pin "44") (pinfunction "AN15/RPB15/PMA0/CTED6//RB15_44") (pintype "bidirectional"))
    )
    (net (code "93") (name "unconnected-(IC1-AN20{slash}PMD2{slash}RE2-Pad98)") (class "Default")
      (node (ref "IC1") (pin "98") (pinfunction "AN20/PMD2/RE2_98") (pintype "bidirectional"))
    )
    (net (code "94") (name "unconnected-(IC1-AN21{slash}PMD4{slash}RE4-Pad100)") (class "Default")
      (node (ref "IC1") (pin "100") (pinfunction "AN21/PMD4/RE4_100") (pintype "bidirectional"))
    )
    (net (code "95") (name "unconnected-(IC1-AN22{slash}RPE5{slash}PMD5{slash}RE5-Pad3)") (class "Default")
      (node (ref "IC1") (pin "3") (pinfunction "AN22/RPE5/PMD5/RE5_3") (pintype "bidirectional"))
    )
    (net (code "96") (name "unconnected-(IC1-AN23{slash}PMD6{slash}RE6-Pad4)") (class "Default")
      (node (ref "IC1") (pin "4") (pinfunction "AN23/PMD6/RE6_4") (pintype "bidirectional"))
    )
    (net (code "97") (name "unconnected-(IC1-AN24{slash}RPD1{slash}RD1-Pad76)") (class "Default")
      (node (ref "IC1") (pin "76") (pinfunction "AN24/RPD1/RD1_76") (pintype "bidirectional"))
    )
    (net (code "98") (name "unconnected-(IC1-AN25{slash}RPD2{slash}RD2-Pad77)") (class "Default")
      (node (ref "IC1") (pin "77") (pinfunction "AN25/RPD2/RD2_77") (pintype "bidirectional"))
    )
    (net (code "99") (name "unconnected-(IC1-AN26{slash}RPD3{slash}RD3-Pad78)") (class "Default")
      (node (ref "IC1") (pin "78") (pinfunction "AN26/RPD3/RD3_78") (pintype "bidirectional"))
    )
    (net (code "100") (name "unconnected-(IC1-AN27{slash}PMD7{slash}RE7-Pad5)") (class "Default")
      (node (ref "IC1") (pin "5") (pinfunction "AN27/PMD7/RE7_5") (pintype "bidirectional"))
    )
    (net (code "101") (name "unconnected-(IC1-CVREFOUT{slash}AN10{slash}RPB10{slash}PMA13{slash}CTED11{slash}RB10-Pad34)") (class "Default")
      (node (ref "IC1") (pin "34") (pinfunction "CVREFOUT/AN10/RPB10/PMA13/CTED11/RB10_34") (pintype "bidirectional"))
    )
    (net (code "102") (name "unconnected-(IC1-PGEC3{slash}AN2{slash}C2INB{slash}RPB2{slash}CTED13{slash}RB2-Pad23)") (class "Default")
      (node (ref "IC1") (pin "23") (pinfunction "PGEC3/AN2/C2INB/RPB2/CTED13/RB2_23") (pintype "bidirectional"))
    )
    (net (code "103") (name "unconnected-(IC1-PMD0{slash}RE0-Pad93)") (class "Default")
      (node (ref "IC1") (pin "93") (pinfunction "PMD0/RE0_93") (pintype "bidirectional"))
    )
    (net (code "104") (name "unconnected-(IC1-PMD1{slash}RE1-Pad94)") (class "Default")
      (node (ref "IC1") (pin "94") (pinfunction "PMD1/RE1_94") (pintype "bidirectional"))
    )
    (net (code "105") (name "unconnected-(IC1-PMD13{slash}RD13-Pad80)") (class "Default")
      (node (ref "IC1") (pin "80") (pinfunction "PMD13/RD13_80") (pintype "bidirectional"))
    )
    (net (code "106") (name "unconnected-(IC1-PMD14{slash}RD6-Pad83)") (class "Default")
      (node (ref "IC1") (pin "83") (pinfunction "PMD14/RD6_83") (pintype "bidirectional"))
    )
    (net (code "107") (name "unconnected-(IC1-RPC1{slash}RC1-Pad6)") (class "Default")
      (node (ref "IC1") (pin "6") (pinfunction "RPC1/RC1_6") (pintype "bidirectional"))
    )
    (net (code "108") (name "unconnected-(IC1-RPC2{slash}RC2-Pad7)") (class "Default")
      (node (ref "IC1") (pin "7") (pinfunction "RPC2/RC2_7") (pintype "bidirectional"))
    )
    (net (code "109") (name "unconnected-(IC1-RPC3{slash}RC3-Pad8)") (class "Default")
      (node (ref "IC1") (pin "8") (pinfunction "RPC3/RC3_8") (pintype "bidirectional"))
    )
    (net (code "110") (name "unconnected-(IC1-RPD0{slash}INT0{slash}RD0-Pad72)") (class "Default")
      (node (ref "IC1") (pin "72") (pinfunction "RPD0/INT0/RD0_72") (pintype "bidirectional"))
    )
    (net (code "111") (name "unconnected-(IC1-RPD4{slash}PMWR{slash}RD4-Pad81)") (class "Default")
      (node (ref "IC1") (pin "81") (pinfunction "RPD4/PMWR/RD4_81") (pintype "bidirectional"))
    )
    (net (code "112") (name "unconnected-(IC1-RPD5{slash}PMRD{slash}RD5-Pad82)") (class "Default")
      (node (ref "IC1") (pin "82") (pinfunction "RPD5/PMRD/RD5_82") (pintype "bidirectional"))
    )
    (net (code "113") (name "unconnected-(IC1-RPD8{slash}RTCC{slash}RD8-Pad68)") (class "Default")
      (node (ref "IC1") (pin "68") (pinfunction "RPD8/RTCC/RD8_68") (pintype "bidirectional"))
    )
    (net (code "114") (name "unconnected-(IC1-RPD9{slash}RD9-Pad69)") (class "Default")
      (node (ref "IC1") (pin "69") (pinfunction "RPD9/RD9_69") (pintype "bidirectional"))
    )
    (net (code "115") (name "unconnected-(IC1-RPD10{slash}SCK1{slash}PMCS2{slash}RD10-Pad70)") (class "Default")
      (node (ref "IC1") (pin "70") (pinfunction "RPD10/SCK1/PMCS2/RD10_70") (pintype "bidirectional"))
    )
    (net (code "116") (name "unconnected-(IC1-RPD11{slash}PMCS1{slash}RD11-Pad71)") (class "Default")
      (node (ref "IC1") (pin "71") (pinfunction "RPD11/PMCS1/RD11_71") (pintype "bidirectional"))
    )
    (net (code "117") (name "unconnected-(IC1-RPD12{slash}PMD12{slash}RD12-Pad79)") (class "Default")
      (node (ref "IC1") (pin "79") (pinfunction "RPD12/PMD12/RD12_79") (pintype "bidirectional"))
    )
    (net (code "118") (name "unconnected-(IC1-RPD14{slash}RD14-Pad47)") (class "Default")
      (node (ref "IC1") (pin "47") (pinfunction "RPD14/RD14_47") (pintype "bidirectional"))
    )
    (net (code "119") (name "unconnected-(IC1-RPD15{slash}RD15-Pad48)") (class "Default")
      (node (ref "IC1") (pin "48") (pinfunction "RPD15/RD15_48") (pintype "bidirectional"))
    )
    (net (code "120") (name "unconnected-(IC1-RPE3{slash}PMD3{slash}RE3-Pad99)") (class "Default")
      (node (ref "IC1") (pin "99") (pinfunction "RPE3/PMD3/RE3_99") (pintype "bidirectional"))
    )
    (net (code "121") (name "unconnected-(IC1-RPE8{slash}RE8-Pad18)") (class "Default")
      (node (ref "IC1") (pin "18") (pinfunction "RPE8/RE8_18") (pintype "bidirectional"))
    )
    (net (code "122") (name "unconnected-(IC1-RPE9{slash}RE9-Pad19)") (class "Default")
      (node (ref "IC1") (pin "19") (pinfunction "RPE9/RE9_19") (pintype "bidirectional"))
    )
    (net (code "123") (name "unconnected-(IC1-RPF3{slash}USBID{slash}RF3-Pad51)") (class "Default")
      (node (ref "IC1") (pin "51") (pinfunction "RPF3/USBID/RF3_51") (pintype "bidirectional"))
    )
    (net (code "124") (name "unconnected-(IC1-RPF4{slash}PMA9{slash}RF4-Pad49)") (class "Default")
      (node (ref "IC1") (pin "49") (pinfunction "RPF4/PMA9/RF4_49") (pintype "bidirectional"))
    )
    (net (code "125") (name "unconnected-(IC1-RPF5{slash}PMA8{slash}RF5-Pad50)") (class "Default")
      (node (ref "IC1") (pin "50") (pinfunction "RPF5/PMA8/RF5_50") (pintype "bidirectional"))
    )
    (net (code "126") (name "unconnected-(IC1-RPF12{slash}RF12-Pad40)") (class "Default")
      (node (ref "IC1") (pin "40") (pinfunction "RPF12/RF12_40") (pintype "bidirectional"))
    )
    (net (code "127") (name "unconnected-(IC1-RPF13{slash}RF13-Pad39)") (class "Default")
      (node (ref "IC1") (pin "39") (pinfunction "RPF13/RF13_39") (pintype "bidirectional"))
    )
    (net (code "128") (name "unconnected-(IC1-RPG0{slash}PMD8{slash}RG0-Pad90)") (class "Default")
      (node (ref "IC1") (pin "90") (pinfunction "RPG0/PMD8/RG0_90") (pintype "bidirectional"))
    )
    (net (code "129") (name "unconnected-(IC1-RPG1{slash}PMD9{slash}RG1-Pad89)") (class "Default")
      (node (ref "IC1") (pin "89") (pinfunction "RPG1/PMD9/RG1_89") (pintype "bidirectional"))
    )
    (net (code "130") (name "unconnected-(IC1-SCL2{slash}RA2-Pad58)") (class "Default")
      (node (ref "IC1") (pin "58") (pinfunction "SCL2/RA2_58") (pintype "bidirectional"))
    )
    (net (code "131") (name "unconnected-(IC1-SDA2{slash}RA3-Pad59)") (class "Default")
      (node (ref "IC1") (pin "59") (pinfunction "SDA2/RA3_59") (pintype "bidirectional"))
    )
    (net (code "132") (name "unconnected-(IC1-SOSCI{slash}RPC13{slash}RC13-Pad73)") (class "Default")
      (node (ref "IC1") (pin "73") (pinfunction "SOSCI/RPC13/RC13_73") (pintype "bidirectional"))
    )
    (net (code "133") (name "unconnected-(IC1-SOSCO{slash}RPC14{slash}T1CK{slash}RC14-Pad74)") (class "Default")
      (node (ref "IC1") (pin "74") (pinfunction "SOSCO/RPC14/T1CK/RC14_74") (pintype "bidirectional"))
    )
    (net (code "134") (name "unconnected-(IC1-TCK{slash}CTED2{slash}RA1-Pad38)") (class "Default")
      (node (ref "IC1") (pin "38") (pinfunction "TCK/CTED2/RA1_38") (pintype "bidirectional"))
    )
    (net (code "135") (name "unconnected-(IC1-TDI{slash}CTED9{slash}RA4-Pad60)") (class "Default")
      (node (ref "IC1") (pin "60") (pinfunction "TDI/CTED9/RA4_60") (pintype "bidirectional"))
    )
    (net (code "136") (name "unconnected-(IC1-TDO{slash}RA5-Pad61)") (class "Default")
      (node (ref "IC1") (pin "61") (pinfunction "TDO/RA5_61") (pintype "bidirectional"))
    )
    (net (code "137") (name "unconnected-(IC1-TMS{slash}CTED1{slash}RA0-Pad17)") (class "Default")
      (node (ref "IC1") (pin "17") (pinfunction "TMS/CTED1/RA0_17") (pintype "bidirectional"))
    )
    (net (code "138") (name "unconnected-(IC1-TRCLK{slash}RA6-Pad91)") (class "Default")
      (node (ref "IC1") (pin "91") (pinfunction "TRCLK/RA6_91") (pintype "bidirectional"))
    )
    (net (code "139") (name "unconnected-(IC1-TRD0{slash}RG13-Pad97)") (class "Default")
      (node (ref "IC1") (pin "97") (pinfunction "TRD0/RG13_97") (pintype "bidirectional"))
    )
    (net (code "140") (name "unconnected-(IC1-TRD2{slash}RG14-Pad95)") (class "Default")
      (node (ref "IC1") (pin "95") (pinfunction "TRD2/RG14_95") (pintype "bidirectional"))
    )
    (net (code "141") (name "unconnected-(IC1-TRD3{slash}CTED8{slash}RA7-Pad92)") (class "Default")
      (node (ref "IC1") (pin "92") (pinfunction "TRD3/CTED8/RA7_92") (pintype "bidirectional"))
    )
    (net (code "142") (name "unconnected-(IC8-PG-Pad9)") (class "Default")
      (node (ref "IC8") (pin "9") (pinfunction "PG_9") (pintype "bidirectional"))
    )
    (net (code "143") (name "unconnected-(Q1A-D-Pad6)") (class "Default")
      (node (ref "Q1") (pin "6") (pinfunction "D_6") (pintype "passive"))
    )
    (net (code "144") (name "unconnected-(Q1A-D1-PadP1)") (class "Default")
      (node (ref "Q1") (pin "P1") (pinfunction "D1_P1") (pintype "passive"))
    )
    (net (code "145") (name "unconnected-(Q1A-G-Pad2)") (class "Default")
      (node (ref "Q1") (pin "2") (pinfunction "G_2") (pintype "passive"))
    )
    (net (code "146") (name "unconnected-(Q1A-S-Pad1)") (class "Default")
      (node (ref "Q1") (pin "1") (pinfunction "S_1") (pintype "passive"))
    )
    (net (code "147") (name "unconnected-(Q2A-D-Pad6)") (class "Default")
      (node (ref "Q2") (pin "6") (pinfunction "D_6") (pintype "passive"))
    )
    (net (code "148") (name "unconnected-(Q2A-D1-PadP1)") (class "Default")
      (node (ref "Q2") (pin "P1") (pinfunction "D1_P1") (pintype "passive"))
    )
    (net (code "149") (name "unconnected-(Q2A-G-Pad2)") (class "Default")
      (node (ref "Q2") (pin "2") (pinfunction "G_2") (pintype "passive"))
    )
    (net (code "150") (name "unconnected-(Q2A-S-Pad1)") (class "Default")
      (node (ref "Q2") (pin "1") (pinfunction "S_1") (pintype "passive"))
    )
  )
)
